# 20230827.net
KiCad netlist of a schematic drawn in EAGLE
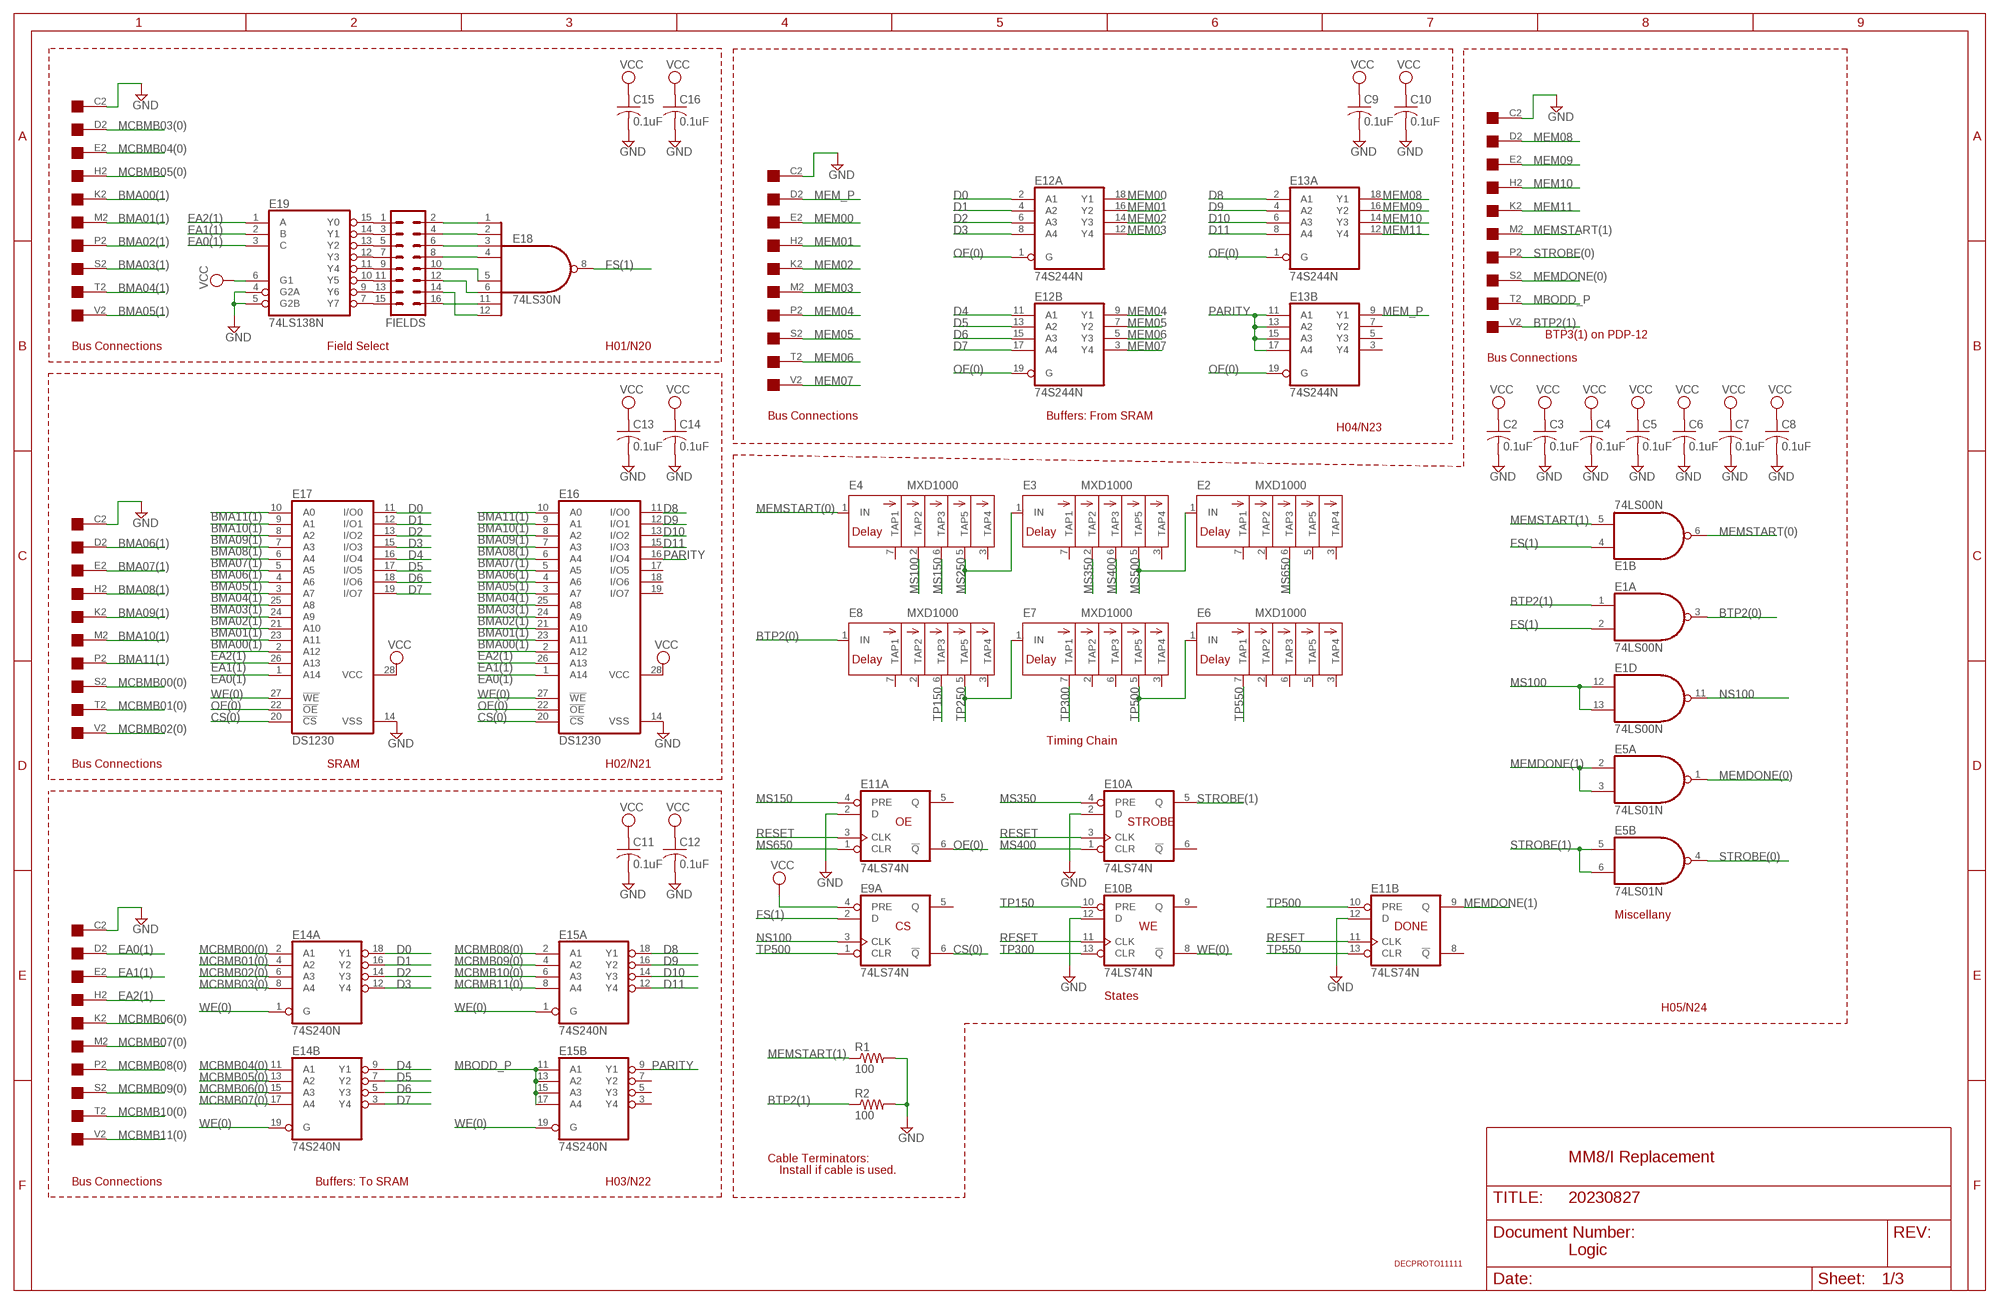
[diagram p0: schematic, sheet 1]
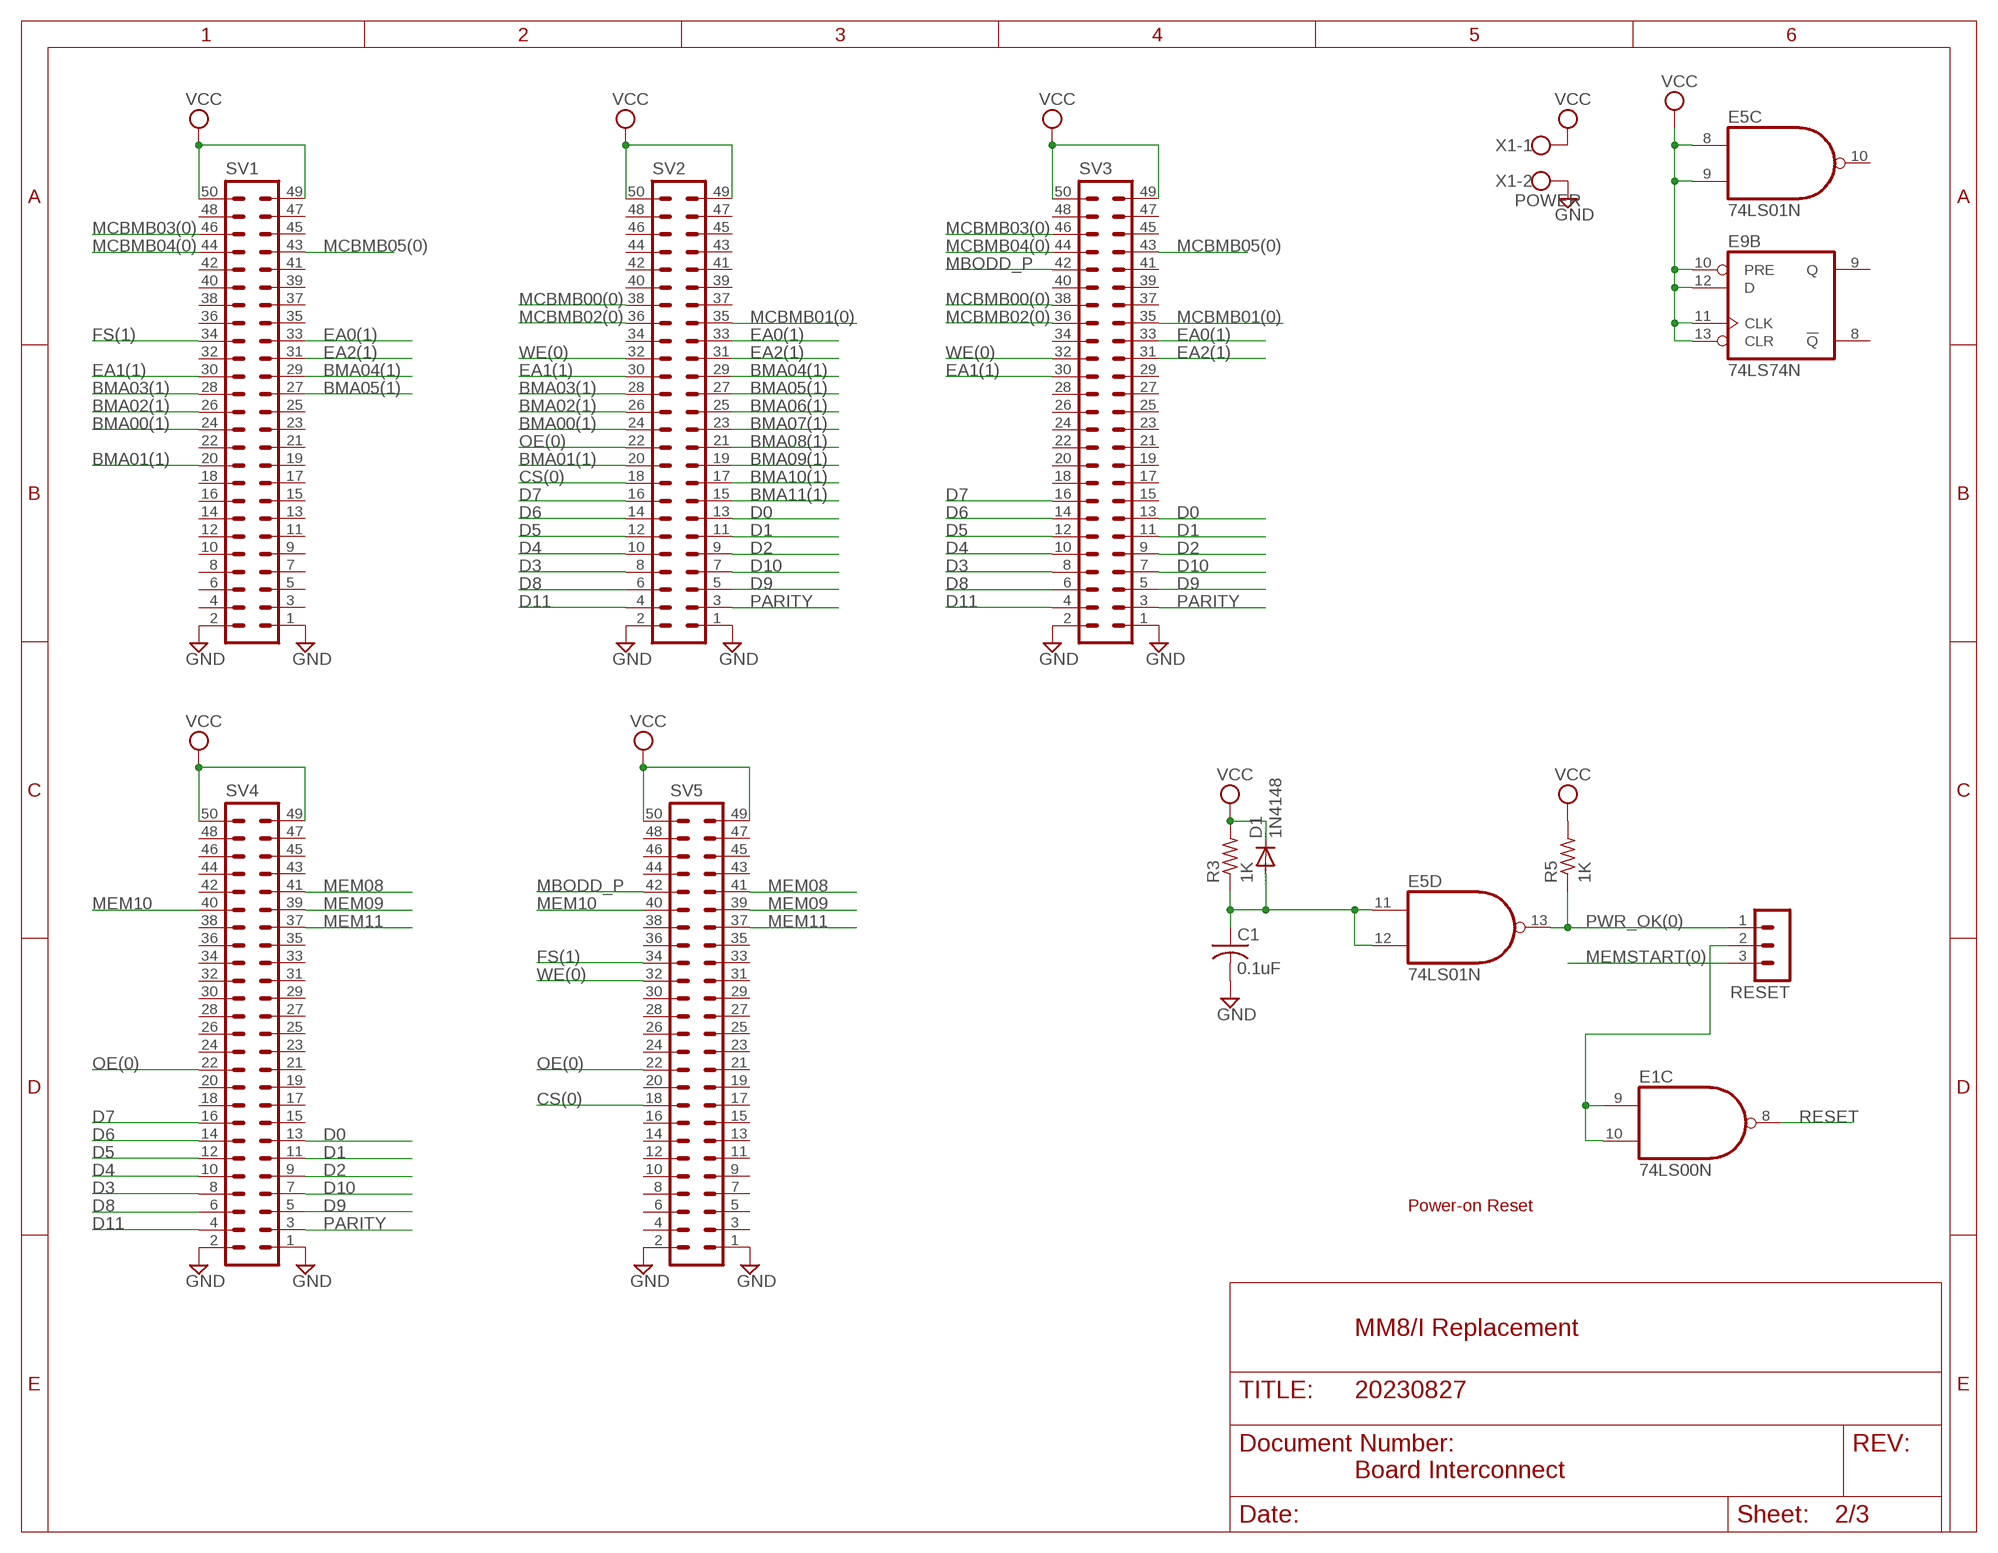
[diagram p1: schematic, sheet 2]
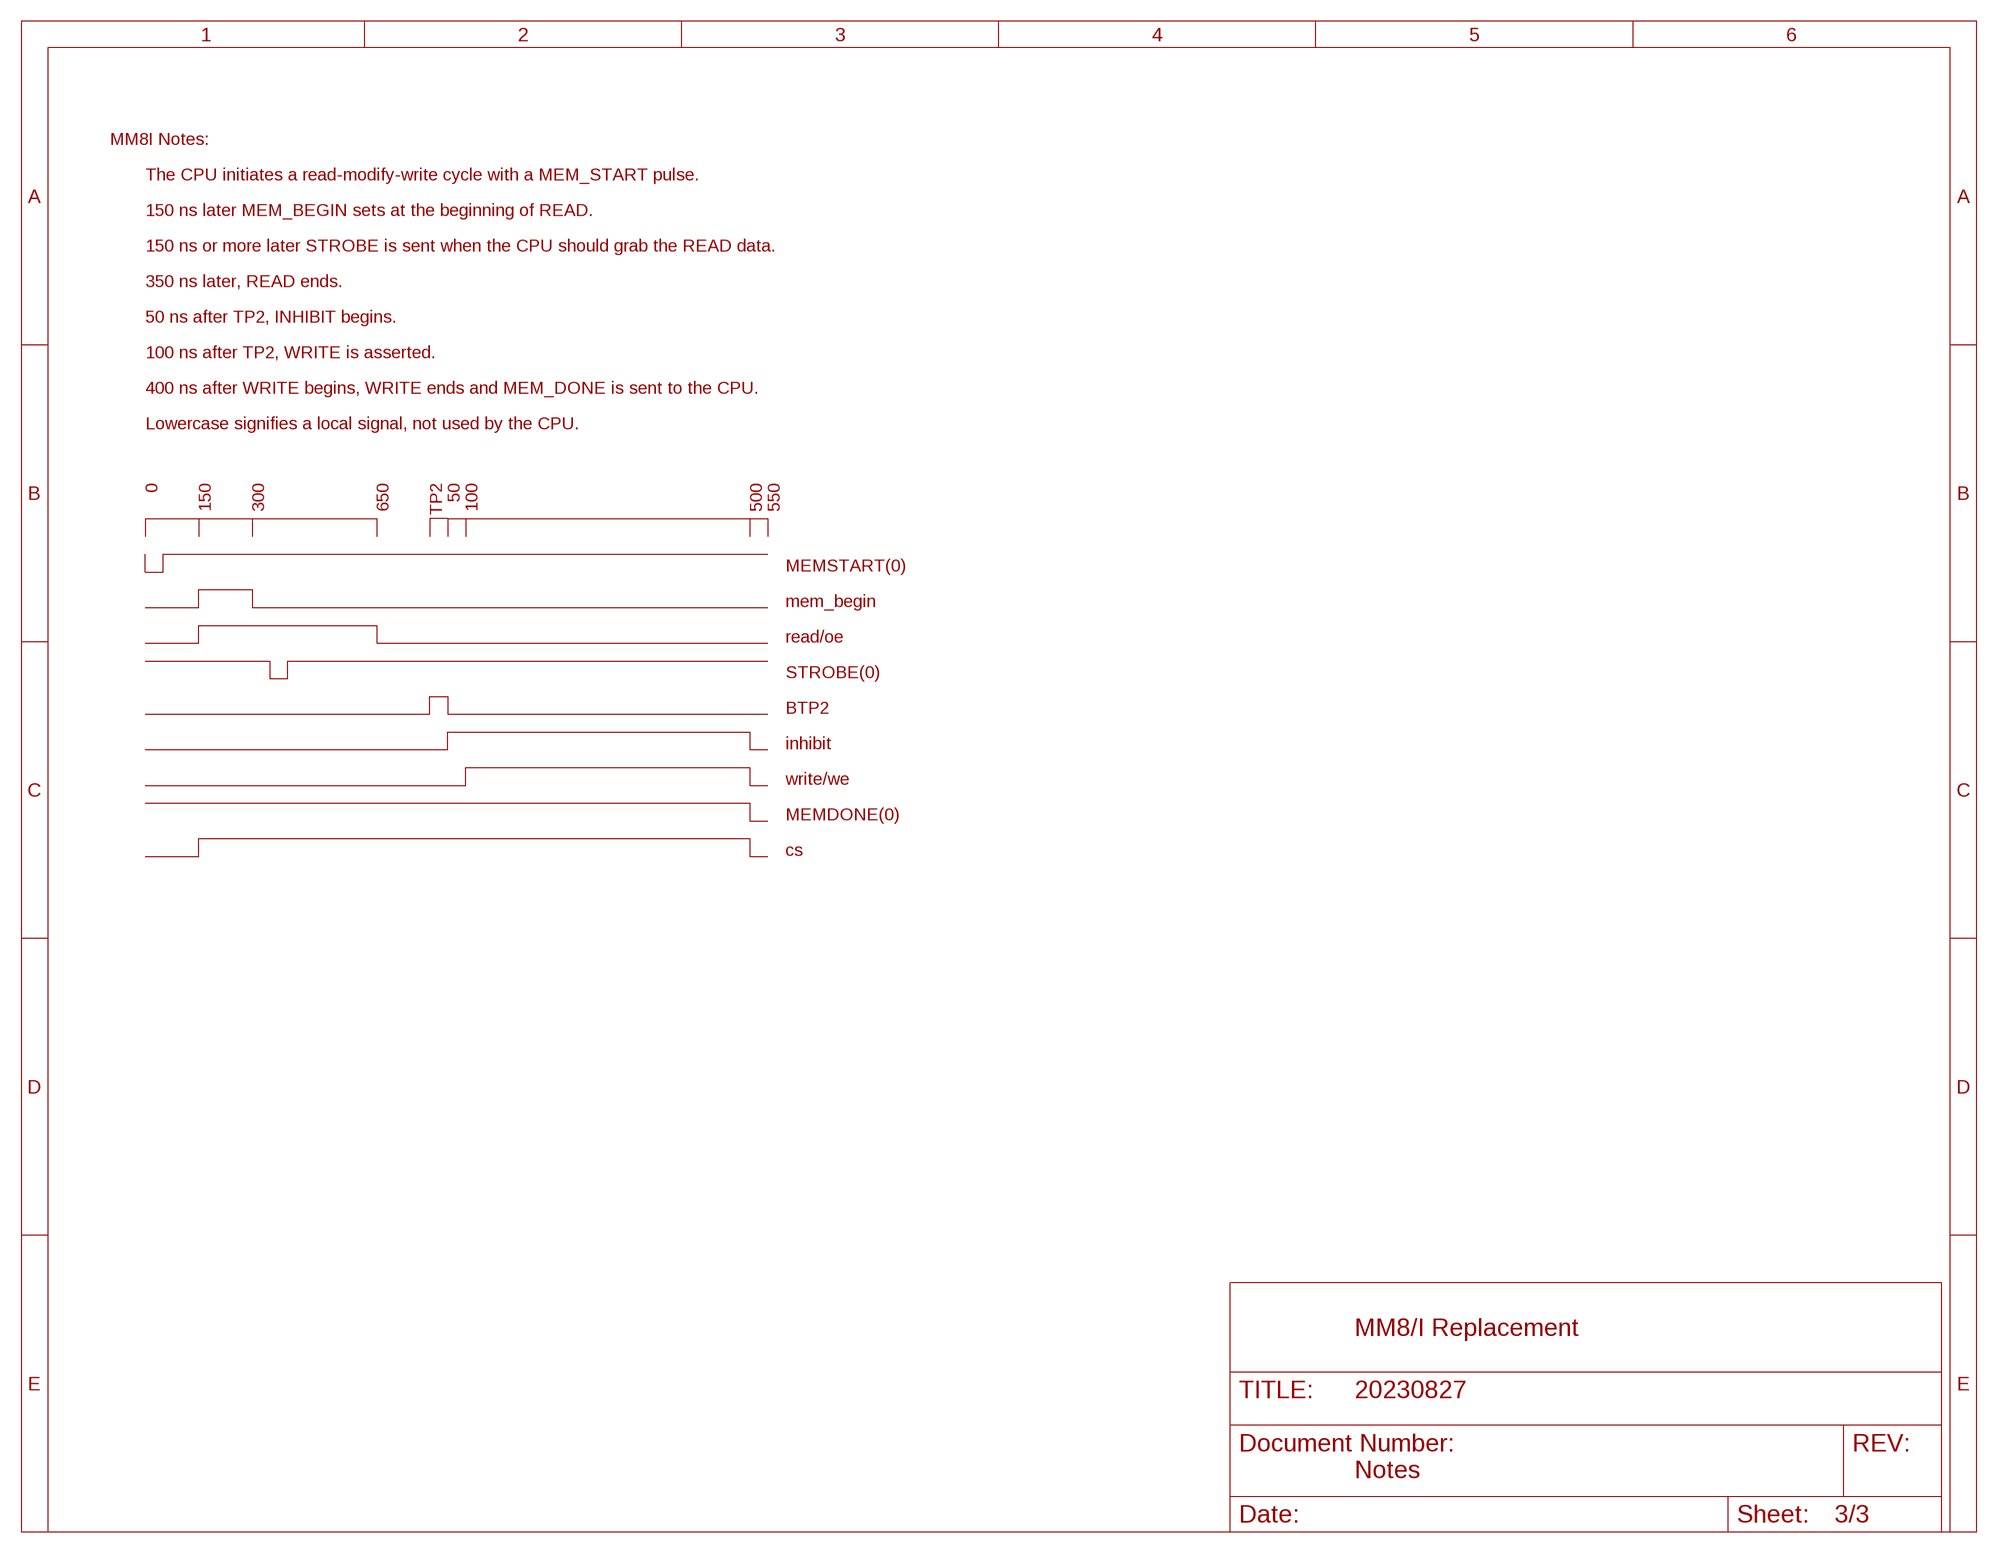
[diagram p2: schematic, sheet 3]

(export (version "E")
  (design (tool "Eeschema 10.0.6"))
  (components
    (comp (ref "C2")
      (value "0.1uF")
      (footprint "eagle-import:C050-025X075")
      (libsource (lib "eagle-import") (part "C-US050-025X075"))
    )
    (comp (ref "C3")
      (value "0.1uF")
      (footprint "eagle-import:C050-025X075")
      (libsource (lib "eagle-import") (part "C-US050-025X075"))
    )
    (comp (ref "C4")
      (value "0.1uF")
      (footprint "eagle-import:C050-025X075")
      (libsource (lib "eagle-import") (part "C-US050-025X075"))
    )
    (comp (ref "C5")
      (value "0.1uF")
      (footprint "eagle-import:C050-025X075")
      (libsource (lib "eagle-import") (part "C-US050-025X075"))
    )
    (comp (ref "C6")
      (value "0.1uF")
      (footprint "eagle-import:C050-025X075")
      (libsource (lib "eagle-import") (part "C-US050-025X075"))
    )
    (comp (ref "C7")
      (value "0.1uF")
      (footprint "eagle-import:C050-025X075")
      (libsource (lib "eagle-import") (part "C-US050-025X075"))
    )
    (comp (ref "C8")
      (value "0.1uF")
      (footprint "eagle-import:C050-025X075")
      (libsource (lib "eagle-import") (part "C-US050-025X075"))
    )
    (comp (ref "C9")
      (value "0.1uF")
      (footprint "eagle-import:C050-025X075")
      (libsource (lib "eagle-import") (part "C-US050-025X075"))
    )
    (comp (ref "C10")
      (value "0.1uF")
      (footprint "eagle-import:C050-025X075")
      (libsource (lib "eagle-import") (part "C-US050-025X075"))
    )
    (comp (ref "C11")
      (value "0.1uF")
      (footprint "eagle-import:C050-025X075")
      (libsource (lib "eagle-import") (part "C-US050-025X075"))
    )
    (comp (ref "C12")
      (value "0.1uF")
      (footprint "eagle-import:C050-025X075")
      (libsource (lib "eagle-import") (part "C-US050-025X075"))
    )
    (comp (ref "C13")
      (value "0.1uF")
      (footprint "eagle-import:C050-025X075")
      (libsource (lib "eagle-import") (part "C-US050-025X075"))
    )
    (comp (ref "C14")
      (value "0.1uF")
      (footprint "eagle-import:C050-025X075")
      (libsource (lib "eagle-import") (part "C-US050-025X075"))
    )
    (comp (ref "C15")
      (value "0.1uF")
      (footprint "eagle-import:C050-025X075")
      (libsource (lib "eagle-import") (part "C-US050-025X075"))
    )
    (comp (ref "C16")
      (value "0.1uF")
      (footprint "eagle-import:C050-025X075")
      (libsource (lib "eagle-import") (part "C-US050-025X075"))
    )
    (comp (ref "E1")
      (value "74LS00N")
      (footprint "eagle-import:DIL14")
      (libsource (lib "eagle-import") (part "7400NLS"))
    )
    (comp (ref "E2")
      (value "MXD1000")
      (footprint "eagle-import:DIL08")
      (libsource (lib "eagle-import") (part "MXD1000"))
    )
    (comp (ref "E3")
      (value "MXD1000")
      (footprint "eagle-import:DIL08")
      (libsource (lib "eagle-import") (part "MXD1000"))
    )
    (comp (ref "E4")
      (value "MXD1000")
      (footprint "eagle-import:DIL08")
      (libsource (lib "eagle-import") (part "MXD1000"))
    )
    (comp (ref "E5")
      (value "74LS01N")
      (footprint "eagle-import:DIL14")
      (libsource (lib "eagle-import") (part "7401NLS"))
    )
    (comp (ref "E6")
      (value "MXD1000")
      (footprint "eagle-import:DIL08")
      (libsource (lib "eagle-import") (part "MXD1000"))
    )
    (comp (ref "E7")
      (value "MXD1000")
      (footprint "eagle-import:DIL08")
      (libsource (lib "eagle-import") (part "MXD1000"))
    )
    (comp (ref "E8")
      (value "MXD1000")
      (footprint "eagle-import:DIL08")
      (libsource (lib "eagle-import") (part "MXD1000"))
    )
    (comp (ref "E9")
      (value "74LS74N")
      (footprint "eagle-import:DIL14")
      (libsource (lib "eagle-import") (part "7474NLS"))
    )
    (comp (ref "E10")
      (value "74LS74N")
      (footprint "eagle-import:DIL14")
      (libsource (lib "eagle-import") (part "7474NLS"))
    )
    (comp (ref "E11")
      (value "74LS74N")
      (footprint "eagle-import:DIL14")
      (libsource (lib "eagle-import") (part "7474NLS"))
    )
    (comp (ref "E12")
      (value "74S244N")
      (footprint "eagle-import:DIL20")
      (libsource (lib "eagle-import") (part "74244NS"))
    )
    (comp (ref "E13")
      (value "74S244N")
      (footprint "eagle-import:DIL20")
      (libsource (lib "eagle-import") (part "74244NS"))
    )
    (comp (ref "E14")
      (value "74S240N")
      (footprint "eagle-import:DIL20")
      (libsource (lib "eagle-import") (part "74240NS"))
    )
    (comp (ref "E15")
      (value "74S240N")
      (footprint "eagle-import:DIL20")
      (libsource (lib "eagle-import") (part "74240NS"))
    )
    (comp (ref "E16")
      (value "DS1230")
      (footprint "eagle-import:DIL28-6")
      (libsource (lib "eagle-import") (part "62256P"))
    )
    (comp (ref "E17")
      (value "DS1230")
      (footprint "eagle-import:DIL28-6")
      (libsource (lib "eagle-import") (part "62256P"))
    )
    (comp (ref "E18")
      (value "74LS30N")
      (footprint "eagle-import:DIL14")
      (libsource (lib "eagle-import") (part "7430NLS"))
    )
    (comp (ref "E19")
      (value "74LS138N")
      (footprint "eagle-import:DIL16")
      (libsource (lib "eagle-import") (part "74138NLS"))
    )
    (comp (ref "FIELDS")
      (value "MA08-2")
      (footprint "eagle-import:MA08-2")
      (libsource (lib "eagle-import") (part "MA08-2"))
    )
    (comp (ref "H01")
      (value "EDGE-1")
      (footprint "eagle-import:EDGE-CON1")
      (libsource (lib "eagle-import") (part "EDGE-1"))
    )
    (comp (ref "H02")
      (value "EDGE-1")
      (footprint "eagle-import:EDGE-CON1")
      (libsource (lib "eagle-import") (part "EDGE-1"))
    )
    (comp (ref "H03")
      (value "EDGE-1")
      (footprint "eagle-import:EDGE-CON1")
      (libsource (lib "eagle-import") (part "EDGE-1"))
    )
    (comp (ref "H04")
      (value "EDGE-1")
      (footprint "eagle-import:EDGE-CON1")
      (libsource (lib "eagle-import") (part "EDGE-1"))
    )
    (comp (ref "H05")
      (value "EDGE-1")
      (footprint "eagle-import:EDGE-CON1")
      (libsource (lib "eagle-import") (part "EDGE-1"))
    )
    (comp (ref "R1")
      (value "100")
      (footprint "eagle-import:0207_10")
      (libsource (lib "eagle-import") (part "R-US_0207/10"))
    )
    (comp (ref "R2")
      (value "100")
      (footprint "eagle-import:0207_10")
      (libsource (lib "eagle-import") (part "R-US_0207/10"))
    )
    (comp (ref "U$6")
      (value "DECPROTO11111")
      (footprint "eagle-import:DECPROTO11111")
      (libsource (lib "eagle-import") (part "DECPROTO11111"))
    )
    (comp (ref "C1")
      (value "0.1uF")
      (footprint "eagle-import:C050-025X075")
      (libsource (lib "eagle-import") (part "C-US050-025X075"))
    )
    (comp (ref "D1")
      (value "1N4148")
      (footprint "eagle-import:DO35-10")
      (libsource (lib "eagle-import") (part "1N4148DO35-10"))
    )
    (comp (ref "R3")
      (value "1K")
      (footprint "eagle-import:0207_10")
      (libsource (lib "eagle-import") (part "R-US_0207/10"))
    )
    (comp (ref "R5")
      (value "1K")
      (footprint "eagle-import:0207_10")
      (libsource (lib "eagle-import") (part "R-US_0207/10"))
    )
    (comp (ref "RESET")
      (value "MA03-1")
      (footprint "eagle-import:MA03-1")
      (libsource (lib "eagle-import") (part "MA03-1"))
    )
    (comp (ref "SV1")
      (value "ML50L")
      (footprint "eagle-import:ML50L")
      (libsource (lib "eagle-import") (part "ML50L"))
    )
    (comp (ref "SV2")
      (value "ML50L")
      (footprint "eagle-import:ML50L")
      (libsource (lib "eagle-import") (part "ML50L"))
    )
    (comp (ref "SV3")
      (value "ML50L")
      (footprint "eagle-import:ML50L")
      (libsource (lib "eagle-import") (part "ML50L"))
    )
    (comp (ref "SV4")
      (value "ML50L")
      (footprint "eagle-import:ML50L")
      (libsource (lib "eagle-import") (part "ML50L"))
    )
    (comp (ref "SV5")
      (value "ML50L")
      (footprint "eagle-import:ML50L")
      (libsource (lib "eagle-import") (part "ML50L"))
    )
    (comp (ref "X1")
      (value "POWER")
      (footprint "eagle-import:W237-102")
      (fields (field (name "MPN") "237-102"))
      (libsource (lib "eagle-import") (part "W237-102"))
    )
  )
  (nets
    (net (code "1") (name "BMA00(1)") (class "Default")
      (node (ref "E16") (pin "23") (pinfunction "A11_23") (pintype "input"))
      (node (ref "E17") (pin "23") (pinfunction "A11_23") (pintype "input"))
      (node (ref "H01") (pin "K2") (pinfunction "1_K2") (pintype "bidirectional"))
      (node (ref "SV1") (pin "24") (pinfunction "24_24") (pintype "passive"))
      (node (ref "SV2") (pin "24") (pinfunction "24_24") (pintype "passive"))
    )
    (net (code "2") (name "BMA01(1)") (class "Default")
      (node (ref "E16") (pin "21") (pinfunction "A10_21") (pintype "input"))
      (node (ref "E17") (pin "21") (pinfunction "A10_21") (pintype "input"))
      (node (ref "H01") (pin "M2") (pinfunction "1_M2") (pintype "bidirectional"))
      (node (ref "SV1") (pin "20") (pinfunction "20_20") (pintype "passive"))
      (node (ref "SV2") (pin "20") (pinfunction "20_20") (pintype "passive"))
    )
    (net (code "3") (name "BMA02(1)") (class "Default")
      (node (ref "E16") (pin "24") (pinfunction "A9_24") (pintype "input"))
      (node (ref "E17") (pin "24") (pinfunction "A9_24") (pintype "input"))
      (node (ref "H01") (pin "P2") (pinfunction "1_P2") (pintype "bidirectional"))
      (node (ref "SV1") (pin "26") (pinfunction "26_26") (pintype "passive"))
      (node (ref "SV2") (pin "26") (pinfunction "26_26") (pintype "passive"))
    )
    (net (code "4") (name "BMA03(1)") (class "Default")
      (node (ref "E16") (pin "25") (pinfunction "A8_25") (pintype "input"))
      (node (ref "E17") (pin "25") (pinfunction "A8_25") (pintype "input"))
      (node (ref "H01") (pin "S2") (pinfunction "1_S2") (pintype "bidirectional"))
      (node (ref "SV1") (pin "28") (pinfunction "28_28") (pintype "passive"))
      (node (ref "SV2") (pin "28") (pinfunction "28_28") (pintype "passive"))
    )
    (net (code "5") (name "BMA04(1)") (class "Default")
      (node (ref "E16") (pin "3") (pinfunction "A7_3") (pintype "input"))
      (node (ref "E17") (pin "3") (pinfunction "A7_3") (pintype "input"))
      (node (ref "H01") (pin "T2") (pinfunction "1_T2") (pintype "bidirectional"))
      (node (ref "SV1") (pin "29") (pinfunction "29_29") (pintype "passive"))
      (node (ref "SV2") (pin "29") (pinfunction "29_29") (pintype "passive"))
    )
    (net (code "6") (name "BMA05(1)") (class "Default")
      (node (ref "E16") (pin "4") (pinfunction "A6_4") (pintype "input"))
      (node (ref "E17") (pin "4") (pinfunction "A6_4") (pintype "input"))
      (node (ref "H01") (pin "V2") (pinfunction "1_V2") (pintype "bidirectional"))
      (node (ref "SV1") (pin "27") (pinfunction "27_27") (pintype "passive"))
      (node (ref "SV2") (pin "27") (pinfunction "27_27") (pintype "passive"))
    )
    (net (code "7") (name "BMA06(1)") (class "Default")
      (node (ref "E16") (pin "5") (pinfunction "A5_5") (pintype "input"))
      (node (ref "E17") (pin "5") (pinfunction "A5_5") (pintype "input"))
      (node (ref "H02") (pin "D2") (pinfunction "1_D2") (pintype "bidirectional"))
      (node (ref "SV2") (pin "25") (pinfunction "25_25") (pintype "passive"))
    )
    (net (code "8") (name "BMA07(1)") (class "Default")
      (node (ref "E16") (pin "6") (pinfunction "A4_6") (pintype "input"))
      (node (ref "E17") (pin "6") (pinfunction "A4_6") (pintype "input"))
      (node (ref "H02") (pin "E2") (pinfunction "1_E2") (pintype "bidirectional"))
      (node (ref "SV2") (pin "23") (pinfunction "23_23") (pintype "passive"))
    )
    (net (code "9") (name "BMA08(1)") (class "Default")
      (node (ref "E16") (pin "7") (pinfunction "A3_7") (pintype "input"))
      (node (ref "E17") (pin "7") (pinfunction "A3_7") (pintype "input"))
      (node (ref "H02") (pin "H2") (pinfunction "1_H2") (pintype "bidirectional"))
      (node (ref "SV2") (pin "21") (pinfunction "21_21") (pintype "passive"))
    )
    (net (code "10") (name "BMA09(1)") (class "Default")
      (node (ref "E16") (pin "8") (pinfunction "A2_8") (pintype "input"))
      (node (ref "E17") (pin "8") (pinfunction "A2_8") (pintype "input"))
      (node (ref "H02") (pin "K2") (pinfunction "1_K2") (pintype "bidirectional"))
      (node (ref "SV2") (pin "19") (pinfunction "19_19") (pintype "passive"))
    )
    (net (code "11") (name "BMA10(1)") (class "Default")
      (node (ref "E16") (pin "9") (pinfunction "A1_9") (pintype "input"))
      (node (ref "E17") (pin "9") (pinfunction "A1_9") (pintype "input"))
      (node (ref "H02") (pin "M2") (pinfunction "1_M2") (pintype "bidirectional"))
      (node (ref "SV2") (pin "17") (pinfunction "17_17") (pintype "passive"))
    )
    (net (code "12") (name "BMA11(1)") (class "Default")
      (node (ref "E16") (pin "10") (pinfunction "A0_10") (pintype "input"))
      (node (ref "E17") (pin "10") (pinfunction "A0_10") (pintype "input"))
      (node (ref "H02") (pin "P2") (pinfunction "1_P2") (pintype "bidirectional"))
      (node (ref "SV2") (pin "15") (pinfunction "15_15") (pintype "passive"))
    )
    (net (code "13") (name "BTP2(0)") (class "Default")
      (node (ref "E1") (pin "3") (pinfunction "O_3") (pintype "output"))
      (node (ref "E8") (pin "1") (pinfunction "IN_1") (pintype "input"))
    )
    (net (code "14") (name "BTP2(1)") (class "Default")
      (node (ref "E1") (pin "1") (pinfunction "I0_1") (pintype "input"))
      (node (ref "H05") (pin "V2") (pinfunction "1_V2") (pintype "bidirectional"))
      (node (ref "R2") (pin "1") (pinfunction "1_1") (pintype "passive"))
    )
    (net (code "15") (name "CS(0)") (class "Default")
      (node (ref "E16") (pin "20") (pinfunction "~{CS}_20") (pintype "input"))
      (node (ref "E17") (pin "20") (pinfunction "~{CS}_20") (pintype "input"))
      (node (ref "E9") (pin "6") (pinfunction "~{Q}_6") (pintype "output"))
      (node (ref "SV2") (pin "18") (pinfunction "18_18") (pintype "passive"))
      (node (ref "SV5") (pin "18") (pinfunction "18_18") (pintype "passive"))
    )
    (net (code "16") (name "D0") (class "Default")
      (node (ref "E12") (pin "2") (pinfunction "A1_2") (pintype "input"))
      (node (ref "E14") (pin "18") (pinfunction "Y1_18") (pintype "tri_state"))
      (node (ref "E17") (pin "11") (pinfunction "I/O0_11") (pintype "bidirectional"))
      (node (ref "SV2") (pin "13") (pinfunction "13_13") (pintype "passive"))
      (node (ref "SV3") (pin "13") (pinfunction "13_13") (pintype "passive"))
      (node (ref "SV4") (pin "13") (pinfunction "13_13") (pintype "passive"))
    )
    (net (code "17") (name "D1") (class "Default")
      (node (ref "E12") (pin "4") (pinfunction "A2_4") (pintype "input"))
      (node (ref "E14") (pin "16") (pinfunction "Y2_16") (pintype "tri_state"))
      (node (ref "E17") (pin "12") (pinfunction "I/O1_12") (pintype "bidirectional"))
      (node (ref "SV2") (pin "11") (pinfunction "11_11") (pintype "passive"))
      (node (ref "SV3") (pin "11") (pinfunction "11_11") (pintype "passive"))
      (node (ref "SV4") (pin "11") (pinfunction "11_11") (pintype "passive"))
    )
    (net (code "18") (name "D2") (class "Default")
      (node (ref "E12") (pin "6") (pinfunction "A3_6") (pintype "input"))
      (node (ref "E14") (pin "14") (pinfunction "Y3_14") (pintype "tri_state"))
      (node (ref "E17") (pin "13") (pinfunction "I/O2_13") (pintype "bidirectional"))
      (node (ref "SV2") (pin "9") (pinfunction "9_9") (pintype "passive"))
      (node (ref "SV3") (pin "9") (pinfunction "9_9") (pintype "passive"))
      (node (ref "SV4") (pin "9") (pinfunction "9_9") (pintype "passive"))
    )
    (net (code "19") (name "D3") (class "Default")
      (node (ref "E12") (pin "8") (pinfunction "A4_8") (pintype "input"))
      (node (ref "E14") (pin "12") (pinfunction "Y4_12") (pintype "tri_state"))
      (node (ref "E17") (pin "15") (pinfunction "I/O3_15") (pintype "bidirectional"))
      (node (ref "SV2") (pin "8") (pinfunction "8_8") (pintype "passive"))
      (node (ref "SV3") (pin "8") (pinfunction "8_8") (pintype "passive"))
      (node (ref "SV4") (pin "8") (pinfunction "8_8") (pintype "passive"))
    )
    (net (code "20") (name "D4") (class "Default")
      (node (ref "E12") (pin "11") (pinfunction "A1_11") (pintype "input"))
      (node (ref "E14") (pin "9") (pinfunction "Y1_9") (pintype "tri_state"))
      (node (ref "E17") (pin "16") (pinfunction "I/O4_16") (pintype "bidirectional"))
      (node (ref "SV2") (pin "10") (pinfunction "10_10") (pintype "passive"))
      (node (ref "SV3") (pin "10") (pinfunction "10_10") (pintype "passive"))
      (node (ref "SV4") (pin "10") (pinfunction "10_10") (pintype "passive"))
    )
    (net (code "21") (name "D5") (class "Default")
      (node (ref "E12") (pin "13") (pinfunction "A2_13") (pintype "input"))
      (node (ref "E14") (pin "7") (pinfunction "Y2_7") (pintype "tri_state"))
      (node (ref "E17") (pin "17") (pinfunction "I/O5_17") (pintype "bidirectional"))
      (node (ref "SV2") (pin "12") (pinfunction "12_12") (pintype "passive"))
      (node (ref "SV3") (pin "12") (pinfunction "12_12") (pintype "passive"))
      (node (ref "SV4") (pin "12") (pinfunction "12_12") (pintype "passive"))
    )
    (net (code "22") (name "D6") (class "Default")
      (node (ref "E12") (pin "15") (pinfunction "A3_15") (pintype "input"))
      (node (ref "E14") (pin "5") (pinfunction "Y3_5") (pintype "tri_state"))
      (node (ref "E17") (pin "18") (pinfunction "I/O6_18") (pintype "bidirectional"))
      (node (ref "SV2") (pin "14") (pinfunction "14_14") (pintype "passive"))
      (node (ref "SV3") (pin "14") (pinfunction "14_14") (pintype "passive"))
      (node (ref "SV4") (pin "14") (pinfunction "14_14") (pintype "passive"))
    )
    (net (code "23") (name "D7") (class "Default")
      (node (ref "E12") (pin "17") (pinfunction "A4_17") (pintype "input"))
      (node (ref "E14") (pin "3") (pinfunction "Y4_3") (pintype "tri_state"))
      (node (ref "E17") (pin "19") (pinfunction "I/O7_19") (pintype "bidirectional"))
      (node (ref "SV2") (pin "16") (pinfunction "16_16") (pintype "passive"))
      (node (ref "SV3") (pin "16") (pinfunction "16_16") (pintype "passive"))
      (node (ref "SV4") (pin "16") (pinfunction "16_16") (pintype "passive"))
    )
    (net (code "24") (name "D8") (class "Default")
      (node (ref "E13") (pin "2") (pinfunction "A1_2") (pintype "input"))
      (node (ref "E15") (pin "18") (pinfunction "Y1_18") (pintype "tri_state"))
      (node (ref "E16") (pin "11") (pinfunction "I/O0_11") (pintype "bidirectional"))
      (node (ref "SV2") (pin "6") (pinfunction "6_6") (pintype "passive"))
      (node (ref "SV3") (pin "6") (pinfunction "6_6") (pintype "passive"))
      (node (ref "SV4") (pin "6") (pinfunction "6_6") (pintype "passive"))
    )
    (net (code "25") (name "D9") (class "Default")
      (node (ref "E13") (pin "4") (pinfunction "A2_4") (pintype "input"))
      (node (ref "E15") (pin "16") (pinfunction "Y2_16") (pintype "tri_state"))
      (node (ref "E16") (pin "12") (pinfunction "I/O1_12") (pintype "bidirectional"))
      (node (ref "SV2") (pin "5") (pinfunction "5_5") (pintype "passive"))
      (node (ref "SV3") (pin "5") (pinfunction "5_5") (pintype "passive"))
      (node (ref "SV4") (pin "5") (pinfunction "5_5") (pintype "passive"))
    )
    (net (code "26") (name "D10") (class "Default")
      (node (ref "E13") (pin "6") (pinfunction "A3_6") (pintype "input"))
      (node (ref "E15") (pin "14") (pinfunction "Y3_14") (pintype "tri_state"))
      (node (ref "E16") (pin "13") (pinfunction "I/O2_13") (pintype "bidirectional"))
      (node (ref "SV2") (pin "7") (pinfunction "7_7") (pintype "passive"))
      (node (ref "SV3") (pin "7") (pinfunction "7_7") (pintype "passive"))
      (node (ref "SV4") (pin "7") (pinfunction "7_7") (pintype "passive"))
    )
    (net (code "27") (name "D11") (class "Default")
      (node (ref "E13") (pin "8") (pinfunction "A4_8") (pintype "input"))
      (node (ref "E15") (pin "12") (pinfunction "Y4_12") (pintype "tri_state"))
      (node (ref "E16") (pin "15") (pinfunction "I/O3_15") (pintype "bidirectional"))
      (node (ref "SV2") (pin "4") (pinfunction "4_4") (pintype "passive"))
      (node (ref "SV3") (pin "4") (pinfunction "4_4") (pintype "passive"))
      (node (ref "SV4") (pin "4") (pinfunction "4_4") (pintype "passive"))
    )
    (net (code "28") (name "EA0(1)") (class "Default")
      (node (ref "E16") (pin "1") (pinfunction "A14_1") (pintype "input"))
      (node (ref "E17") (pin "1") (pinfunction "A14_1") (pintype "input"))
      (node (ref "E19") (pin "3") (pinfunction "C_3") (pintype "input"))
      (node (ref "H03") (pin "D2") (pinfunction "1_D2") (pintype "bidirectional"))
      (node (ref "SV1") (pin "33") (pinfunction "33_33") (pintype "passive"))
      (node (ref "SV2") (pin "33") (pinfunction "33_33") (pintype "passive"))
      (node (ref "SV3") (pin "33") (pinfunction "33_33") (pintype "passive"))
    )
    (net (code "29") (name "EA1(1)") (class "Default")
      (node (ref "E16") (pin "26") (pinfunction "A13_26") (pintype "input"))
      (node (ref "E17") (pin "26") (pinfunction "A13_26") (pintype "input"))
      (node (ref "E19") (pin "2") (pinfunction "B_2") (pintype "input"))
      (node (ref "H03") (pin "E2") (pinfunction "1_E2") (pintype "bidirectional"))
      (node (ref "SV1") (pin "30") (pinfunction "30_30") (pintype "passive"))
      (node (ref "SV2") (pin "30") (pinfunction "30_30") (pintype "passive"))
      (node (ref "SV3") (pin "30") (pinfunction "30_30") (pintype "passive"))
    )
    (net (code "30") (name "EA2(1)") (class "Default")
      (node (ref "E16") (pin "2") (pinfunction "A12_2") (pintype "input"))
      (node (ref "E17") (pin "2") (pinfunction "A12_2") (pintype "input"))
      (node (ref "E19") (pin "1") (pinfunction "A_1") (pintype "input"))
      (node (ref "H03") (pin "H2") (pinfunction "1_H2") (pintype "bidirectional"))
      (node (ref "SV1") (pin "31") (pinfunction "31_31") (pintype "passive"))
      (node (ref "SV2") (pin "31") (pinfunction "31_31") (pintype "passive"))
      (node (ref "SV3") (pin "31") (pinfunction "31_31") (pintype "passive"))
    )
    (net (code "31") (name "FS(1)") (class "Default")
      (node (ref "E1") (pin "2") (pinfunction "I1_2") (pintype "input"))
      (node (ref "E1") (pin "4") (pinfunction "I0_4") (pintype "input"))
      (node (ref "E18") (pin "8") (pinfunction "O_8") (pintype "output"))
      (node (ref "E9") (pin "2") (pinfunction "D_2") (pintype "input"))
      (node (ref "SV1") (pin "34") (pinfunction "34_34") (pintype "passive"))
      (node (ref "SV5") (pin "34") (pinfunction "34_34") (pintype "passive"))
    )
    (net (code "32") (name "GND") (class "Default")
      (node (ref "C1") (pin "2") (pinfunction "2_2") (pintype "passive"))
      (node (ref "C10") (pin "2") (pinfunction "2_2") (pintype "passive"))
      (node (ref "C11") (pin "2") (pinfunction "2_2") (pintype "passive"))
      (node (ref "C12") (pin "2") (pinfunction "2_2") (pintype "passive"))
      (node (ref "C13") (pin "2") (pinfunction "2_2") (pintype "passive"))
      (node (ref "C14") (pin "2") (pinfunction "2_2") (pintype "passive"))
      (node (ref "C15") (pin "2") (pinfunction "2_2") (pintype "passive"))
      (node (ref "C16") (pin "2") (pinfunction "2_2") (pintype "passive"))
      (node (ref "C2") (pin "2") (pinfunction "2_2") (pintype "passive"))
      (node (ref "C3") (pin "2") (pinfunction "2_2") (pintype "passive"))
      (node (ref "C4") (pin "2") (pinfunction "2_2") (pintype "passive"))
      (node (ref "C5") (pin "2") (pinfunction "2_2") (pintype "passive"))
      (node (ref "C6") (pin "2") (pinfunction "2_2") (pintype "passive"))
      (node (ref "C7") (pin "2") (pinfunction "2_2") (pintype "passive"))
      (node (ref "C8") (pin "2") (pinfunction "2_2") (pintype "passive"))
      (node (ref "C9") (pin "2") (pinfunction "2_2") (pintype "passive"))
      (node (ref "E10") (pin "12") (pinfunction "D_12") (pintype "input"))
      (node (ref "E10") (pin "2") (pinfunction "D_2") (pintype "input"))
      (node (ref "E11") (pin "12") (pinfunction "D_12") (pintype "input"))
      (node (ref "E11") (pin "2") (pinfunction "D_2") (pintype "input"))
      (node (ref "E16") (pin "14") (pinfunction "VSS_14") (pintype "power_in"))
      (node (ref "E17") (pin "14") (pinfunction "VSS_14") (pintype "power_in"))
      (node (ref "E19") (pin "4") (pinfunction "G2A_4") (pintype "input"))
      (node (ref "E19") (pin "5") (pinfunction "G2B_5") (pintype "input"))
      (node (ref "H01") (pin "C2") (pinfunction "1_C2") (pintype "bidirectional"))
      (node (ref "H02") (pin "C2") (pinfunction "1_C2") (pintype "bidirectional"))
      (node (ref "H03") (pin "C2") (pinfunction "1_C2") (pintype "bidirectional"))
      (node (ref "H04") (pin "C2") (pinfunction "1_C2") (pintype "bidirectional"))
      (node (ref "H05") (pin "C2") (pinfunction "1_C2") (pintype "bidirectional"))
      (node (ref "R1") (pin "2") (pinfunction "2_2") (pintype "passive"))
      (node (ref "R2") (pin "2") (pinfunction "2_2") (pintype "passive"))
      (node (ref "SV1") (pin "1") (pinfunction "1_1") (pintype "passive"))
      (node (ref "SV1") (pin "2") (pinfunction "2_2") (pintype "passive"))
      (node (ref "SV2") (pin "1") (pinfunction "1_1") (pintype "passive"))
      (node (ref "SV2") (pin "2") (pinfunction "2_2") (pintype "passive"))
      (node (ref "SV3") (pin "1") (pinfunction "1_1") (pintype "passive"))
      (node (ref "SV3") (pin "2") (pinfunction "2_2") (pintype "passive"))
      (node (ref "SV4") (pin "1") (pinfunction "1_1") (pintype "passive"))
      (node (ref "SV4") (pin "2") (pinfunction "2_2") (pintype "passive"))
      (node (ref "SV5") (pin "1") (pinfunction "1_1") (pintype "passive"))
      (node (ref "SV5") (pin "2") (pinfunction "2_2") (pintype "passive"))
      (node (ref "X1") (pin "2") (pinfunction "KL_2") (pintype "passive"))
    )
    (net (code "33") (name "MBODD_P") (class "Default")
      (node (ref "E15") (pin "11") (pinfunction "A1_11") (pintype "input"))
      (node (ref "E15") (pin "13") (pinfunction "A2_13") (pintype "input"))
      (node (ref "E15") (pin "15") (pinfunction "A3_15") (pintype "input"))
      (node (ref "E15") (pin "17") (pinfunction "A4_17") (pintype "input"))
      (node (ref "H05") (pin "T2") (pinfunction "1_T2") (pintype "bidirectional"))
      (node (ref "SV3") (pin "42") (pinfunction "42_42") (pintype "passive"))
      (node (ref "SV5") (pin "42") (pinfunction "42_42") (pintype "passive"))
    )
    (net (code "34") (name "MCBMB00(0)") (class "Default")
      (node (ref "E14") (pin "2") (pinfunction "A1_2") (pintype "input"))
      (node (ref "H02") (pin "S2") (pinfunction "1_S2") (pintype "bidirectional"))
      (node (ref "SV2") (pin "38") (pinfunction "38_38") (pintype "passive"))
      (node (ref "SV3") (pin "38") (pinfunction "38_38") (pintype "passive"))
    )
    (net (code "35") (name "MCBMB01(0)") (class "Default")
      (node (ref "E14") (pin "4") (pinfunction "A2_4") (pintype "input"))
      (node (ref "H02") (pin "T2") (pinfunction "1_T2") (pintype "bidirectional"))
      (node (ref "SV2") (pin "35") (pinfunction "35_35") (pintype "passive"))
      (node (ref "SV3") (pin "35") (pinfunction "35_35") (pintype "passive"))
    )
    (net (code "36") (name "MCBMB02(0)") (class "Default")
      (node (ref "E14") (pin "6") (pinfunction "A3_6") (pintype "input"))
      (node (ref "H02") (pin "V2") (pinfunction "1_V2") (pintype "bidirectional"))
      (node (ref "SV2") (pin "36") (pinfunction "36_36") (pintype "passive"))
      (node (ref "SV3") (pin "36") (pinfunction "36_36") (pintype "passive"))
    )
    (net (code "37") (name "MCBMB03(0)") (class "Default")
      (node (ref "E14") (pin "8") (pinfunction "A4_8") (pintype "input"))
      (node (ref "H01") (pin "D2") (pinfunction "1_D2") (pintype "bidirectional"))
      (node (ref "SV1") (pin "46") (pinfunction "46_46") (pintype "passive"))
      (node (ref "SV3") (pin "46") (pinfunction "46_46") (pintype "passive"))
    )
    (net (code "38") (name "MCBMB04(0)") (class "Default")
      (node (ref "E14") (pin "11") (pinfunction "A1_11") (pintype "input"))
      (node (ref "H01") (pin "E2") (pinfunction "1_E2") (pintype "bidirectional"))
      (node (ref "SV1") (pin "44") (pinfunction "44_44") (pintype "passive"))
      (node (ref "SV3") (pin "44") (pinfunction "44_44") (pintype "passive"))
    )
    (net (code "39") (name "MCBMB05(0)") (class "Default")
      (node (ref "E14") (pin "13") (pinfunction "A2_13") (pintype "input"))
      (node (ref "H01") (pin "H2") (pinfunction "1_H2") (pintype "bidirectional"))
      (node (ref "SV1") (pin "43") (pinfunction "43_43") (pintype "passive"))
      (node (ref "SV3") (pin "43") (pinfunction "43_43") (pintype "passive"))
    )
    (net (code "40") (name "MCBMB06(0)") (class "Default")
      (node (ref "E14") (pin "15") (pinfunction "A3_15") (pintype "input"))
      (node (ref "H03") (pin "K2") (pinfunction "1_K2") (pintype "bidirectional"))
    )
    (net (code "41") (name "MCBMB07(0)") (class "Default")
      (node (ref "E14") (pin "17") (pinfunction "A4_17") (pintype "input"))
      (node (ref "H03") (pin "M2") (pinfunction "1_M2") (pintype "bidirectional"))
    )
    (net (code "42") (name "MCBMB08(0)") (class "Default")
      (node (ref "E15") (pin "2") (pinfunction "A1_2") (pintype "input"))
      (node (ref "H03") (pin "P2") (pinfunction "1_P2") (pintype "bidirectional"))
    )
    (net (code "43") (name "MCBMB09(0)") (class "Default")
      (node (ref "E15") (pin "4") (pinfunction "A2_4") (pintype "input"))
      (node (ref "H03") (pin "S2") (pinfunction "1_S2") (pintype "bidirectional"))
    )
    (net (code "44") (name "MCBMB10(0)") (class "Default")
      (node (ref "E15") (pin "6") (pinfunction "A3_6") (pintype "input"))
      (node (ref "H03") (pin "T2") (pinfunction "1_T2") (pintype "bidirectional"))
    )
    (net (code "45") (name "MCBMB11(0)") (class "Default")
      (node (ref "E15") (pin "8") (pinfunction "A4_8") (pintype "input"))
      (node (ref "H03") (pin "V2") (pinfunction "1_V2") (pintype "bidirectional"))
    )
    (net (code "46") (name "MEM00") (class "Default")
      (node (ref "E12") (pin "18") (pinfunction "Y1_18") (pintype "tri_state"))
      (node (ref "H04") (pin "E2") (pinfunction "1_E2") (pintype "bidirectional"))
    )
    (net (code "47") (name "MEM01") (class "Default")
      (node (ref "E12") (pin "16") (pinfunction "Y2_16") (pintype "tri_state"))
      (node (ref "H04") (pin "H2") (pinfunction "1_H2") (pintype "bidirectional"))
    )
    (net (code "48") (name "MEM02") (class "Default")
      (node (ref "E12") (pin "14") (pinfunction "Y3_14") (pintype "tri_state"))
      (node (ref "H04") (pin "K2") (pinfunction "1_K2") (pintype "bidirectional"))
    )
    (net (code "49") (name "MEM03") (class "Default")
      (node (ref "E12") (pin "12") (pinfunction "Y4_12") (pintype "tri_state"))
      (node (ref "H04") (pin "M2") (pinfunction "1_M2") (pintype "bidirectional"))
    )
    (net (code "50") (name "MEM04") (class "Default")
      (node (ref "E12") (pin "9") (pinfunction "Y1_9") (pintype "tri_state"))
      (node (ref "H04") (pin "P2") (pinfunction "1_P2") (pintype "bidirectional"))
    )
    (net (code "51") (name "MEM05") (class "Default")
      (node (ref "E12") (pin "7") (pinfunction "Y2_7") (pintype "tri_state"))
      (node (ref "H04") (pin "S2") (pinfunction "1_S2") (pintype "bidirectional"))
    )
    (net (code "52") (name "MEM06") (class "Default")
      (node (ref "E12") (pin "5") (pinfunction "Y3_5") (pintype "tri_state"))
      (node (ref "H04") (pin "T2") (pinfunction "1_T2") (pintype "bidirectional"))
    )
    (net (code "53") (name "MEM07") (class "Default")
      (node (ref "E12") (pin "3") (pinfunction "Y4_3") (pintype "tri_state"))
      (node (ref "H04") (pin "V2") (pinfunction "1_V2") (pintype "bidirectional"))
    )
    (net (code "54") (name "MEM08") (class "Default")
      (node (ref "E13") (pin "18") (pinfunction "Y1_18") (pintype "tri_state"))
      (node (ref "H05") (pin "D2") (pinfunction "1_D2") (pintype "bidirectional"))
      (node (ref "SV4") (pin "41") (pinfunction "41_41") (pintype "passive"))
      (node (ref "SV5") (pin "41") (pinfunction "41_41") (pintype "passive"))
    )
    (net (code "55") (name "MEM09") (class "Default")
      (node (ref "E13") (pin "16") (pinfunction "Y2_16") (pintype "tri_state"))
      (node (ref "H05") (pin "E2") (pinfunction "1_E2") (pintype "bidirectional"))
      (node (ref "SV4") (pin "39") (pinfunction "39_39") (pintype "passive"))
      (node (ref "SV5") (pin "39") (pinfunction "39_39") (pintype "passive"))
    )
    (net (code "56") (name "MEM10") (class "Default")
      (node (ref "E13") (pin "14") (pinfunction "Y3_14") (pintype "tri_state"))
      (node (ref "H05") (pin "H2") (pinfunction "1_H2") (pintype "bidirectional"))
      (node (ref "SV4") (pin "40") (pinfunction "40_40") (pintype "passive"))
      (node (ref "SV5") (pin "40") (pinfunction "40_40") (pintype "passive"))
    )
    (net (code "57") (name "MEM11") (class "Default")
      (node (ref "E13") (pin "12") (pinfunction "Y4_12") (pintype "tri_state"))
      (node (ref "H05") (pin "K2") (pinfunction "1_K2") (pintype "bidirectional"))
      (node (ref "SV4") (pin "37") (pinfunction "37_37") (pintype "passive"))
      (node (ref "SV5") (pin "37") (pinfunction "37_37") (pintype "passive"))
    )
    (net (code "58") (name "MEMDONE(0)") (class "Default")
      (node (ref "E5") (pin "1") (pinfunction "O_1") (pintype "open_collector"))
      (node (ref "H05") (pin "S2") (pinfunction "1_S2") (pintype "bidirectional"))
    )
    (net (code "59") (name "MEMDONE(1)") (class "Default")
      (node (ref "E11") (pin "9") (pinfunction "Q_9") (pintype "output"))
      (node (ref "E5") (pin "2") (pinfunction "I0_2") (pintype "input"))
      (node (ref "E5") (pin "3") (pinfunction "I1_3") (pintype "input"))
    )
    (net (code "60") (name "MEMSTART(0)") (class "Default")
      (node (ref "E1") (pin "6") (pinfunction "O_6") (pintype "output"))
      (node (ref "E4") (pin "1") (pinfunction "IN_1") (pintype "input"))
      (node (ref "RESET") (pin "3") (pinfunction "3_3") (pintype "passive"))
    )
    (net (code "61") (name "MEMSTART(1)") (class "Default")
      (node (ref "E1") (pin "5") (pinfunction "I1_5") (pintype "input"))
      (node (ref "H05") (pin "M2") (pinfunction "1_M2") (pintype "bidirectional"))
      (node (ref "R1") (pin "1") (pinfunction "1_1") (pintype "passive"))
    )
    (net (code "62") (name "MEM_P") (class "Default")
      (node (ref "E13") (pin "9") (pinfunction "Y1_9") (pintype "tri_state"))
      (node (ref "H04") (pin "D2") (pinfunction "1_D2") (pintype "bidirectional"))
    )
    (net (code "63") (name "MS100") (class "Default")
      (node (ref "E1") (pin "12") (pinfunction "I0_12") (pintype "input"))
      (node (ref "E1") (pin "13") (pinfunction "I1_13") (pintype "input"))
      (node (ref "E4") (pin "2") (pinfunction "TAP2_2") (pintype "output"))
    )
    (net (code "64") (name "MS150") (class "Default")
      (node (ref "E11") (pin "4") (pinfunction "PRE_4") (pintype "input"))
      (node (ref "E4") (pin "6") (pinfunction "TAP3_6") (pintype "output"))
    )
    (net (code "65") (name "MS250") (class "Default")
      (node (ref "E3") (pin "1") (pinfunction "IN_1") (pintype "input"))
      (node (ref "E4") (pin "5") (pinfunction "TAP5_5") (pintype "output"))
    )
    (net (code "66") (name "MS350") (class "Default")
      (node (ref "E10") (pin "4") (pinfunction "PRE_4") (pintype "input"))
      (node (ref "E3") (pin "2") (pinfunction "TAP2_2") (pintype "output"))
    )
    (net (code "67") (name "MS400") (class "Default")
      (node (ref "E10") (pin "1") (pinfunction "CLR_1") (pintype "input"))
      (node (ref "E3") (pin "6") (pinfunction "TAP3_6") (pintype "output"))
    )
    (net (code "68") (name "MS500") (class "Default")
      (node (ref "E2") (pin "1") (pinfunction "IN_1") (pintype "input"))
      (node (ref "E3") (pin "5") (pinfunction "TAP5_5") (pintype "output"))
    )
    (net (code "69") (name "MS650") (class "Default")
      (node (ref "E11") (pin "1") (pinfunction "CLR_1") (pintype "input"))
      (node (ref "E2") (pin "6") (pinfunction "TAP3_6") (pintype "output"))
    )
    (net (code "70") (name "NS100") (class "Default")
      (node (ref "E1") (pin "11") (pinfunction "O_11") (pintype "output"))
      (node (ref "E9") (pin "3") (pinfunction "CLK_3") (pintype "input"))
    )
    (net (code "71") (name "Net-(E1C-I0)") (class "Default")
      (node (ref "E1") (pin "10") (pinfunction "I1_10") (pintype "input"))
      (node (ref "E1") (pin "9") (pinfunction "I0_9") (pintype "input"))
      (node (ref "RESET") (pin "2") (pinfunction "2_2") (pintype "passive"))
    )
    (net (code "72") (name "Net-(E5D-I0)") (class "Default")
      (node (ref "C1") (pin "1") (pinfunction "1_1") (pintype "passive"))
      (node (ref "D1") (pin "A") (pinfunction "A_A") (pintype "passive"))
      (node (ref "E5") (pin "11") (pinfunction "I0_11") (pintype "input"))
      (node (ref "E5") (pin "12") (pinfunction "I1_12") (pintype "input"))
      (node (ref "R3") (pin "1") (pinfunction "1_1") (pintype "passive"))
    )
    (net (code "73") (name "Net-(E18A-I0)") (class "Default")
      (node (ref "E18") (pin "1") (pinfunction "I0_1") (pintype "input"))
      (node (ref "FIELDS") (pin "2") (pinfunction "2_2") (pintype "passive"))
    )
    (net (code "74") (name "Net-(E18A-I1)") (class "Default")
      (node (ref "E18") (pin "2") (pinfunction "I1_2") (pintype "input"))
      (node (ref "FIELDS") (pin "4") (pinfunction "4_4") (pintype "passive"))
    )
    (net (code "75") (name "Net-(E18A-I2)") (class "Default")
      (node (ref "E18") (pin "3") (pinfunction "I2_3") (pintype "input"))
      (node (ref "FIELDS") (pin "6") (pinfunction "6_6") (pintype "passive"))
    )
    (net (code "76") (name "Net-(E18A-I3)") (class "Default")
      (node (ref "E18") (pin "4") (pinfunction "I3_4") (pintype "input"))
      (node (ref "FIELDS") (pin "8") (pinfunction "8_8") (pintype "passive"))
    )
    (net (code "77") (name "Net-(E18A-I4)") (class "Default")
      (node (ref "E18") (pin "5") (pinfunction "I4_5") (pintype "input"))
      (node (ref "FIELDS") (pin "10") (pinfunction "10_10") (pintype "passive"))
    )
    (net (code "78") (name "Net-(E18A-I5)") (class "Default")
      (node (ref "E18") (pin "6") (pinfunction "I5_6") (pintype "input"))
      (node (ref "FIELDS") (pin "12") (pinfunction "12_12") (pintype "passive"))
    )
    (net (code "79") (name "Net-(E18A-I6)") (class "Default")
      (node (ref "E18") (pin "11") (pinfunction "I6_11") (pintype "input"))
      (node (ref "FIELDS") (pin "16") (pinfunction "16_16") (pintype "passive"))
    )
    (net (code "80") (name "Net-(E18A-I7)") (class "Default")
      (node (ref "E18") (pin "12") (pinfunction "I7_12") (pintype "input"))
      (node (ref "FIELDS") (pin "14") (pinfunction "14_14") (pintype "passive"))
    )
    (net (code "81") (name "Net-(E19A-Y0)") (class "Default")
      (node (ref "E19") (pin "15") (pinfunction "Y0_15") (pintype "output"))
      (node (ref "FIELDS") (pin "1") (pinfunction "1_1") (pintype "passive"))
    )
    (net (code "82") (name "Net-(E19A-Y1)") (class "Default")
      (node (ref "E19") (pin "14") (pinfunction "Y1_14") (pintype "output"))
      (node (ref "FIELDS") (pin "3") (pinfunction "3_3") (pintype "passive"))
    )
    (net (code "83") (name "Net-(E19A-Y2)") (class "Default")
      (node (ref "E19") (pin "13") (pinfunction "Y2_13") (pintype "output"))
      (node (ref "FIELDS") (pin "5") (pinfunction "5_5") (pintype "passive"))
    )
    (net (code "84") (name "Net-(E19A-Y3)") (class "Default")
      (node (ref "E19") (pin "12") (pinfunction "Y3_12") (pintype "output"))
      (node (ref "FIELDS") (pin "7") (pinfunction "7_7") (pintype "passive"))
    )
    (net (code "85") (name "Net-(E19A-Y4)") (class "Default")
      (node (ref "E19") (pin "11") (pinfunction "Y4_11") (pintype "output"))
      (node (ref "FIELDS") (pin "9") (pinfunction "9_9") (pintype "passive"))
    )
    (net (code "86") (name "Net-(E19A-Y5)") (class "Default")
      (node (ref "E19") (pin "10") (pinfunction "Y5_10") (pintype "output"))
      (node (ref "FIELDS") (pin "11") (pinfunction "11_11") (pintype "passive"))
    )
    (net (code "87") (name "Net-(E19A-Y6)") (class "Default")
      (node (ref "E19") (pin "9") (pinfunction "Y6_9") (pintype "output"))
      (node (ref "FIELDS") (pin "13") (pinfunction "13_13") (pintype "passive"))
    )
    (net (code "88") (name "Net-(E19A-Y7)") (class "Default")
      (node (ref "E19") (pin "7") (pinfunction "Y7_7") (pintype "output"))
      (node (ref "FIELDS") (pin "15") (pinfunction "15_15") (pintype "passive"))
    )
    (net (code "89") (name "OE(0)") (class "Default")
      (node (ref "E11") (pin "6") (pinfunction "~{Q}_6") (pintype "output"))
      (node (ref "E12") (pin "1") (pinfunction "G_1") (pintype "input"))
      (node (ref "E12") (pin "19") (pinfunction "G_19") (pintype "input"))
      (node (ref "E13") (pin "1") (pinfunction "G_1") (pintype "input"))
      (node (ref "E13") (pin "19") (pinfunction "G_19") (pintype "input"))
      (node (ref "E16") (pin "22") (pinfunction "~{OE}_22") (pintype "input"))
      (node (ref "E17") (pin "22") (pinfunction "~{OE}_22") (pintype "input"))
      (node (ref "SV2") (pin "22") (pinfunction "22_22") (pintype "passive"))
      (node (ref "SV4") (pin "22") (pinfunction "22_22") (pintype "passive"))
      (node (ref "SV5") (pin "22") (pinfunction "22_22") (pintype "passive"))
    )
    (net (code "90") (name "PARITY") (class "Default")
      (node (ref "E13") (pin "11") (pinfunction "A1_11") (pintype "input"))
      (node (ref "E13") (pin "13") (pinfunction "A2_13") (pintype "input"))
      (node (ref "E13") (pin "15") (pinfunction "A3_15") (pintype "input"))
      (node (ref "E13") (pin "17") (pinfunction "A4_17") (pintype "input"))
      (node (ref "E15") (pin "9") (pinfunction "Y1_9") (pintype "tri_state"))
      (node (ref "E16") (pin "16") (pinfunction "I/O4_16") (pintype "bidirectional"))
      (node (ref "SV2") (pin "3") (pinfunction "3_3") (pintype "passive"))
      (node (ref "SV3") (pin "3") (pinfunction "3_3") (pintype "passive"))
      (node (ref "SV4") (pin "3") (pinfunction "3_3") (pintype "passive"))
    )
    (net (code "91") (name "PWR_OK(0)") (class "Default")
      (node (ref "E5") (pin "13") (pinfunction "O_13") (pintype "open_collector"))
      (node (ref "R5") (pin "1") (pinfunction "1_1") (pintype "passive"))
      (node (ref "RESET") (pin "1") (pinfunction "1_1") (pintype "passive"))
    )
    (net (code "92") (name "RESET") (class "Default")
      (node (ref "E1") (pin "8") (pinfunction "O_8") (pintype "output"))
      (node (ref "E10") (pin "11") (pinfunction "CLK_11") (pintype "input"))
      (node (ref "E10") (pin "3") (pinfunction "CLK_3") (pintype "input"))
      (node (ref "E11") (pin "11") (pinfunction "CLK_11") (pintype "input"))
      (node (ref "E11") (pin "3") (pinfunction "CLK_3") (pintype "input"))
    )
    (net (code "93") (name "STROBE(0)") (class "Default")
      (node (ref "E5") (pin "4") (pinfunction "O_4") (pintype "open_collector"))
      (node (ref "H05") (pin "P2") (pinfunction "1_P2") (pintype "bidirectional"))
    )
    (net (code "94") (name "STROBE(1)") (class "Default")
      (node (ref "E10") (pin "5") (pinfunction "Q_5") (pintype "output"))
      (node (ref "E5") (pin "5") (pinfunction "I0_5") (pintype "input"))
      (node (ref "E5") (pin "6") (pinfunction "I1_6") (pintype "input"))
    )
    (net (code "95") (name "TP150") (class "Default")
      (node (ref "E10") (pin "10") (pinfunction "PRE_10") (pintype "input"))
      (node (ref "E8") (pin "6") (pinfunction "TAP3_6") (pintype "output"))
    )
    (net (code "96") (name "TP250") (class "Default")
      (node (ref "E7") (pin "1") (pinfunction "IN_1") (pintype "input"))
      (node (ref "E8") (pin "5") (pinfunction "TAP5_5") (pintype "output"))
    )
    (net (code "97") (name "TP300") (class "Default")
      (node (ref "E10") (pin "13") (pinfunction "CLR_13") (pintype "input"))
      (node (ref "E7") (pin "7") (pinfunction "TAP1_7") (pintype "output"))
    )
    (net (code "98") (name "TP500") (class "Default")
      (node (ref "E11") (pin "10") (pinfunction "PRE_10") (pintype "input"))
      (node (ref "E6") (pin "1") (pinfunction "IN_1") (pintype "input"))
      (node (ref "E7") (pin "5") (pinfunction "TAP5_5") (pintype "output"))
      (node (ref "E9") (pin "1") (pinfunction "CLR_1") (pintype "input"))
    )
    (net (code "99") (name "TP550") (class "Default")
      (node (ref "E11") (pin "13") (pinfunction "CLR_13") (pintype "input"))
      (node (ref "E6") (pin "7") (pinfunction "TAP1_7") (pintype "output"))
    )
    (net (code "100") (name "VCC") (class "Default")
      (node (ref "C10") (pin "1") (pinfunction "1_1") (pintype "passive"))
      (node (ref "C11") (pin "1") (pinfunction "1_1") (pintype "passive"))
      (node (ref "C12") (pin "1") (pinfunction "1_1") (pintype "passive"))
      (node (ref "C13") (pin "1") (pinfunction "1_1") (pintype "passive"))
      (node (ref "C14") (pin "1") (pinfunction "1_1") (pintype "passive"))
      (node (ref "C15") (pin "1") (pinfunction "1_1") (pintype "passive"))
      (node (ref "C16") (pin "1") (pinfunction "1_1") (pintype "passive"))
      (node (ref "C2") (pin "1") (pinfunction "1_1") (pintype "passive"))
      (node (ref "C3") (pin "1") (pinfunction "1_1") (pintype "passive"))
      (node (ref "C4") (pin "1") (pinfunction "1_1") (pintype "passive"))
      (node (ref "C5") (pin "1") (pinfunction "1_1") (pintype "passive"))
      (node (ref "C6") (pin "1") (pinfunction "1_1") (pintype "passive"))
      (node (ref "C7") (pin "1") (pinfunction "1_1") (pintype "passive"))
      (node (ref "C8") (pin "1") (pinfunction "1_1") (pintype "passive"))
      (node (ref "C9") (pin "1") (pinfunction "1_1") (pintype "passive"))
      (node (ref "D1") (pin "C") (pinfunction "C_C") (pintype "passive"))
      (node (ref "E16") (pin "28") (pinfunction "VCC_28") (pintype "power_in"))
      (node (ref "E17") (pin "28") (pinfunction "VCC_28") (pintype "power_in"))
      (node (ref "E19") (pin "6") (pinfunction "G1_6") (pintype "input"))
      (node (ref "E5") (pin "8") (pinfunction "I0_8") (pintype "input"))
      (node (ref "E5") (pin "9") (pinfunction "I1_9") (pintype "input"))
      (node (ref "E9") (pin "10") (pinfunction "PRE_10") (pintype "input"))
      (node (ref "E9") (pin "11") (pinfunction "CLK_11") (pintype "input"))
      (node (ref "E9") (pin "12") (pinfunction "D_12") (pintype "input"))
      (node (ref "E9") (pin "13") (pinfunction "CLR_13") (pintype "input"))
      (node (ref "E9") (pin "4") (pinfunction "PRE_4") (pintype "input"))
      (node (ref "R3") (pin "2") (pinfunction "2_2") (pintype "passive"))
      (node (ref "R5") (pin "2") (pinfunction "2_2") (pintype "passive"))
      (node (ref "SV1") (pin "49") (pinfunction "49_49") (pintype "passive"))
      (node (ref "SV1") (pin "50") (pinfunction "50_50") (pintype "passive"))
      (node (ref "SV2") (pin "49") (pinfunction "49_49") (pintype "passive"))
      (node (ref "SV2") (pin "50") (pinfunction "50_50") (pintype "passive"))
      (node (ref "SV3") (pin "49") (pinfunction "49_49") (pintype "passive"))
      (node (ref "SV3") (pin "50") (pinfunction "50_50") (pintype "passive"))
      (node (ref "SV4") (pin "49") (pinfunction "49_49") (pintype "passive"))
      (node (ref "SV4") (pin "50") (pinfunction "50_50") (pintype "passive"))
      (node (ref "SV5") (pin "49") (pinfunction "49_49") (pintype "passive"))
      (node (ref "SV5") (pin "50") (pinfunction "50_50") (pintype "passive"))
      (node (ref "X1") (pin "1") (pinfunction "KL_1") (pintype "passive"))
    )
    (net (code "101") (name "WE(0)") (class "Default")
      (node (ref "E10") (pin "8") (pinfunction "~{Q}_8") (pintype "output"))
      (node (ref "E14") (pin "1") (pinfunction "G_1") (pintype "input"))
      (node (ref "E14") (pin "19") (pinfunction "G_19") (pintype "input"))
      (node (ref "E15") (pin "1") (pinfunction "G_1") (pintype "input"))
      (node (ref "E15") (pin "19") (pinfunction "G_19") (pintype "input"))
      (node (ref "E16") (pin "27") (pinfunction "~{WE}_27") (pintype "input"))
      (node (ref "E17") (pin "27") (pinfunction "~{WE}_27") (pintype "input"))
      (node (ref "SV2") (pin "32") (pinfunction "32_32") (pintype "passive"))
      (node (ref "SV3") (pin "32") (pinfunction "32_32") (pintype "passive"))
      (node (ref "SV5") (pin "32") (pinfunction "32_32") (pintype "passive"))
    )
    (net (code "102") (name "unconnected-(E2A-TAP1-Pad7)") (class "Default")
      (node (ref "E2") (pin "7") (pinfunction "TAP1_7") (pintype "output"))
    )
    (net (code "103") (name "unconnected-(E2A-TAP2-Pad2)") (class "Default")
      (node (ref "E2") (pin "2") (pinfunction "TAP2_2") (pintype "output"))
    )
    (net (code "104") (name "unconnected-(E2A-TAP4-Pad3)") (class "Default")
      (node (ref "E2") (pin "3") (pinfunction "TAP4_3") (pintype "output"))
    )
    (net (code "105") (name "unconnected-(E2A-TAP5-Pad5)") (class "Default")
      (node (ref "E2") (pin "5") (pinfunction "TAP5_5") (pintype "output"))
    )
    (net (code "106") (name "unconnected-(E3A-TAP1-Pad7)") (class "Default")
      (node (ref "E3") (pin "7") (pinfunction "TAP1_7") (pintype "output"))
    )
    (net (code "107") (name "unconnected-(E3A-TAP4-Pad3)") (class "Default")
      (node (ref "E3") (pin "3") (pinfunction "TAP4_3") (pintype "output"))
    )
    (net (code "108") (name "unconnected-(E4A-TAP1-Pad7)") (class "Default")
      (node (ref "E4") (pin "7") (pinfunction "TAP1_7") (pintype "output"))
    )
    (net (code "109") (name "unconnected-(E4A-TAP4-Pad3)") (class "Default")
      (node (ref "E4") (pin "3") (pinfunction "TAP4_3") (pintype "output"))
    )
    (net (code "110") (name "unconnected-(E5C-O-Pad10)") (class "Default")
      (node (ref "E5") (pin "10") (pinfunction "O_10") (pintype "open_collector"))
    )
    (net (code "111") (name "unconnected-(E6A-TAP2-Pad2)") (class "Default")
      (node (ref "E6") (pin "2") (pinfunction "TAP2_2") (pintype "output"))
    )
    (net (code "112") (name "unconnected-(E6A-TAP3-Pad6)") (class "Default")
      (node (ref "E6") (pin "6") (pinfunction "TAP3_6") (pintype "output"))
    )
    (net (code "113") (name "unconnected-(E6A-TAP4-Pad3)") (class "Default")
      (node (ref "E6") (pin "3") (pinfunction "TAP4_3") (pintype "output"))
    )
    (net (code "114") (name "unconnected-(E6A-TAP5-Pad5)") (class "Default")
      (node (ref "E6") (pin "5") (pinfunction "TAP5_5") (pintype "output"))
    )
    (net (code "115") (name "unconnected-(E7A-TAP2-Pad2)") (class "Default")
      (node (ref "E7") (pin "2") (pinfunction "TAP2_2") (pintype "output"))
    )
    (net (code "116") (name "unconnected-(E7A-TAP3-Pad6)") (class "Default")
      (node (ref "E7") (pin "6") (pinfunction "TAP3_6") (pintype "output"))
    )
    (net (code "117") (name "unconnected-(E7A-TAP4-Pad3)") (class "Default")
      (node (ref "E7") (pin "3") (pinfunction "TAP4_3") (pintype "output"))
    )
    (net (code "118") (name "unconnected-(E8A-TAP1-Pad7)") (class "Default")
      (node (ref "E8") (pin "7") (pinfunction "TAP1_7") (pintype "output"))
    )
    (net (code "119") (name "unconnected-(E8A-TAP2-Pad2)") (class "Default")
      (node (ref "E8") (pin "2") (pinfunction "TAP2_2") (pintype "output"))
    )
    (net (code "120") (name "unconnected-(E8A-TAP4-Pad3)") (class "Default")
      (node (ref "E8") (pin "3") (pinfunction "TAP4_3") (pintype "output"))
    )
    (net (code "121") (name "unconnected-(E9A-Q-Pad5)") (class "Default")
      (node (ref "E9") (pin "5") (pinfunction "Q_5") (pintype "output"))
    )
    (net (code "122") (name "unconnected-(E9B-Q-Pad9)") (class "Default")
      (node (ref "E9") (pin "9") (pinfunction "Q_9") (pintype "output"))
    )
    (net (code "123") (name "unconnected-(E9B-~{Q}-Pad8)") (class "Default")
      (node (ref "E9") (pin "8") (pinfunction "~{Q}_8") (pintype "output"))
    )
    (net (code "124") (name "unconnected-(E10A-~{Q}-Pad6)") (class "Default")
      (node (ref "E10") (pin "6") (pinfunction "~{Q}_6") (pintype "output"))
    )
    (net (code "125") (name "unconnected-(E10B-Q-Pad9)") (class "Default")
      (node (ref "E10") (pin "9") (pinfunction "Q_9") (pintype "output"))
    )
    (net (code "126") (name "unconnected-(E11A-Q-Pad5)") (class "Default")
      (node (ref "E11") (pin "5") (pinfunction "Q_5") (pintype "output"))
    )
    (net (code "127") (name "unconnected-(E11B-~{Q}-Pad8)") (class "Default")
      (node (ref "E11") (pin "8") (pinfunction "~{Q}_8") (pintype "output"))
    )
    (net (code "128") (name "unconnected-(E13B-Y2-Pad7)") (class "Default")
      (node (ref "E13") (pin "7") (pinfunction "Y2_7") (pintype "tri_state"))
    )
    (net (code "129") (name "unconnected-(E13B-Y3-Pad5)") (class "Default")
      (node (ref "E13") (pin "5") (pinfunction "Y3_5") (pintype "tri_state"))
    )
    (net (code "130") (name "unconnected-(E13B-Y4-Pad3)") (class "Default")
      (node (ref "E13") (pin "3") (pinfunction "Y4_3") (pintype "tri_state"))
    )
    (net (code "131") (name "unconnected-(E15B-Y2-Pad7)") (class "Default")
      (node (ref "E15") (pin "7") (pinfunction "Y2_7") (pintype "tri_state"))
    )
    (net (code "132") (name "unconnected-(E15B-Y3-Pad5)") (class "Default")
      (node (ref "E15") (pin "5") (pinfunction "Y3_5") (pintype "tri_state"))
    )
    (net (code "133") (name "unconnected-(E15B-Y4-Pad3)") (class "Default")
      (node (ref "E15") (pin "3") (pinfunction "Y4_3") (pintype "tri_state"))
    )
    (net (code "134") (name "unconnected-(E16-I{slash}O5-Pad17)") (class "Default")
      (node (ref "E16") (pin "17") (pinfunction "I/O5_17") (pintype "bidirectional"))
    )
    (net (code "135") (name "unconnected-(E16-I{slash}O6-Pad18)") (class "Default")
      (node (ref "E16") (pin "18") (pinfunction "I/O6_18") (pintype "bidirectional"))
    )
    (net (code "136") (name "unconnected-(E16-I{slash}O7-Pad19)") (class "Default")
      (node (ref "E16") (pin "19") (pinfunction "I/O7_19") (pintype "bidirectional"))
    )
    (net (code "137") (name "unconnected-(SV1-Pad3)") (class "Default")
      (node (ref "SV1") (pin "3") (pinfunction "3_3") (pintype "passive"))
    )
    (net (code "138") (name "unconnected-(SV1-Pad4)") (class "Default")
      (node (ref "SV1") (pin "4") (pinfunction "4_4") (pintype "passive"))
    )
    (net (code "139") (name "unconnected-(SV1-Pad5)") (class "Default")
      (node (ref "SV1") (pin "5") (pinfunction "5_5") (pintype "passive"))
    )
    (net (code "140") (name "unconnected-(SV1-Pad6)") (class "Default")
      (node (ref "SV1") (pin "6") (pinfunction "6_6") (pintype "passive"))
    )
    (net (code "141") (name "unconnected-(SV1-Pad7)") (class "Default")
      (node (ref "SV1") (pin "7") (pinfunction "7_7") (pintype "passive"))
    )
    (net (code "142") (name "unconnected-(SV1-Pad8)") (class "Default")
      (node (ref "SV1") (pin "8") (pinfunction "8_8") (pintype "passive"))
    )
    (net (code "143") (name "unconnected-(SV1-Pad9)") (class "Default")
      (node (ref "SV1") (pin "9") (pinfunction "9_9") (pintype "passive"))
    )
    (net (code "144") (name "unconnected-(SV1-Pad10)") (class "Default")
      (node (ref "SV1") (pin "10") (pinfunction "10_10") (pintype "passive"))
    )
    (net (code "145") (name "unconnected-(SV1-Pad11)") (class "Default")
      (node (ref "SV1") (pin "11") (pinfunction "11_11") (pintype "passive"))
    )
    (net (code "146") (name "unconnected-(SV1-Pad12)") (class "Default")
      (node (ref "SV1") (pin "12") (pinfunction "12_12") (pintype "passive"))
    )
    (net (code "147") (name "unconnected-(SV1-Pad13)") (class "Default")
      (node (ref "SV1") (pin "13") (pinfunction "13_13") (pintype "passive"))
    )
    (net (code "148") (name "unconnected-(SV1-Pad14)") (class "Default")
      (node (ref "SV1") (pin "14") (pinfunction "14_14") (pintype "passive"))
    )
    (net (code "149") (name "unconnected-(SV1-Pad15)") (class "Default")
      (node (ref "SV1") (pin "15") (pinfunction "15_15") (pintype "passive"))
    )
    (net (code "150") (name "unconnected-(SV1-Pad16)") (class "Default")
      (node (ref "SV1") (pin "16") (pinfunction "16_16") (pintype "passive"))
    )
    (net (code "151") (name "unconnected-(SV1-Pad17)") (class "Default")
      (node (ref "SV1") (pin "17") (pinfunction "17_17") (pintype "passive"))
    )
    (net (code "152") (name "unconnected-(SV1-Pad18)") (class "Default")
      (node (ref "SV1") (pin "18") (pinfunction "18_18") (pintype "passive"))
    )
    (net (code "153") (name "unconnected-(SV1-Pad19)") (class "Default")
      (node (ref "SV1") (pin "19") (pinfunction "19_19") (pintype "passive"))
    )
    (net (code "154") (name "unconnected-(SV1-Pad21)") (class "Default")
      (node (ref "SV1") (pin "21") (pinfunction "21_21") (pintype "passive"))
    )
    (net (code "155") (name "unconnected-(SV1-Pad22)") (class "Default")
      (node (ref "SV1") (pin "22") (pinfunction "22_22") (pintype "passive"))
    )
    (net (code "156") (name "unconnected-(SV1-Pad23)") (class "Default")
      (node (ref "SV1") (pin "23") (pinfunction "23_23") (pintype "passive"))
    )
    (net (code "157") (name "unconnected-(SV1-Pad25)") (class "Default")
      (node (ref "SV1") (pin "25") (pinfunction "25_25") (pintype "passive"))
    )
    (net (code "158") (name "unconnected-(SV1-Pad32)") (class "Default")
      (node (ref "SV1") (pin "32") (pinfunction "32_32") (pintype "passive"))
    )
    (net (code "159") (name "unconnected-(SV1-Pad35)") (class "Default")
      (node (ref "SV1") (pin "35") (pinfunction "35_35") (pintype "passive"))
    )
    (net (code "160") (name "unconnected-(SV1-Pad36)") (class "Default")
      (node (ref "SV1") (pin "36") (pinfunction "36_36") (pintype "passive"))
    )
    (net (code "161") (name "unconnected-(SV1-Pad37)") (class "Default")
      (node (ref "SV1") (pin "37") (pinfunction "37_37") (pintype "passive"))
    )
    (net (code "162") (name "unconnected-(SV1-Pad38)") (class "Default")
      (node (ref "SV1") (pin "38") (pinfunction "38_38") (pintype "passive"))
    )
    (net (code "163") (name "unconnected-(SV1-Pad39)") (class "Default")
      (node (ref "SV1") (pin "39") (pinfunction "39_39") (pintype "passive"))
    )
    (net (code "164") (name "unconnected-(SV1-Pad40)") (class "Default")
      (node (ref "SV1") (pin "40") (pinfunction "40_40") (pintype "passive"))
    )
    (net (code "165") (name "unconnected-(SV1-Pad41)") (class "Default")
      (node (ref "SV1") (pin "41") (pinfunction "41_41") (pintype "passive"))
    )
    (net (code "166") (name "unconnected-(SV1-Pad42)") (class "Default")
      (node (ref "SV1") (pin "42") (pinfunction "42_42") (pintype "passive"))
    )
    (net (code "167") (name "unconnected-(SV1-Pad45)") (class "Default")
      (node (ref "SV1") (pin "45") (pinfunction "45_45") (pintype "passive"))
    )
    (net (code "168") (name "unconnected-(SV1-Pad47)") (class "Default")
      (node (ref "SV1") (pin "47") (pinfunction "47_47") (pintype "passive"))
    )
    (net (code "169") (name "unconnected-(SV1-Pad48)") (class "Default")
      (node (ref "SV1") (pin "48") (pinfunction "48_48") (pintype "passive"))
    )
    (net (code "170") (name "unconnected-(SV2-Pad34)") (class "Default")
      (node (ref "SV2") (pin "34") (pinfunction "34_34") (pintype "passive"))
    )
    (net (code "171") (name "unconnected-(SV2-Pad37)") (class "Default")
      (node (ref "SV2") (pin "37") (pinfunction "37_37") (pintype "passive"))
    )
    (net (code "172") (name "unconnected-(SV2-Pad39)") (class "Default")
      (node (ref "SV2") (pin "39") (pinfunction "39_39") (pintype "passive"))
    )
    (net (code "173") (name "unconnected-(SV2-Pad40)") (class "Default")
      (node (ref "SV2") (pin "40") (pinfunction "40_40") (pintype "passive"))
    )
    (net (code "174") (name "unconnected-(SV2-Pad41)") (class "Default")
      (node (ref "SV2") (pin "41") (pinfunction "41_41") (pintype "passive"))
    )
    (net (code "175") (name "unconnected-(SV2-Pad42)") (class "Default")
      (node (ref "SV2") (pin "42") (pinfunction "42_42") (pintype "passive"))
    )
    (net (code "176") (name "unconnected-(SV2-Pad43)") (class "Default")
      (node (ref "SV2") (pin "43") (pinfunction "43_43") (pintype "passive"))
    )
    (net (code "177") (name "unconnected-(SV2-Pad44)") (class "Default")
      (node (ref "SV2") (pin "44") (pinfunction "44_44") (pintype "passive"))
    )
    (net (code "178") (name "unconnected-(SV2-Pad45)") (class "Default")
      (node (ref "SV2") (pin "45") (pinfunction "45_45") (pintype "passive"))
    )
    (net (code "179") (name "unconnected-(SV2-Pad46)") (class "Default")
      (node (ref "SV2") (pin "46") (pinfunction "46_46") (pintype "passive"))
    )
    (net (code "180") (name "unconnected-(SV2-Pad47)") (class "Default")
      (node (ref "SV2") (pin "47") (pinfunction "47_47") (pintype "passive"))
    )
    (net (code "181") (name "unconnected-(SV2-Pad48)") (class "Default")
      (node (ref "SV2") (pin "48") (pinfunction "48_48") (pintype "passive"))
    )
    (net (code "182") (name "unconnected-(SV3-Pad15)") (class "Default")
      (node (ref "SV3") (pin "15") (pinfunction "15_15") (pintype "passive"))
    )
    (net (code "183") (name "unconnected-(SV3-Pad17)") (class "Default")
      (node (ref "SV3") (pin "17") (pinfunction "17_17") (pintype "passive"))
    )
    (net (code "184") (name "unconnected-(SV3-Pad18)") (class "Default")
      (node (ref "SV3") (pin "18") (pinfunction "18_18") (pintype "passive"))
    )
    (net (code "185") (name "unconnected-(SV3-Pad19)") (class "Default")
      (node (ref "SV3") (pin "19") (pinfunction "19_19") (pintype "passive"))
    )
    (net (code "186") (name "unconnected-(SV3-Pad20)") (class "Default")
      (node (ref "SV3") (pin "20") (pinfunction "20_20") (pintype "passive"))
    )
    (net (code "187") (name "unconnected-(SV3-Pad21)") (class "Default")
      (node (ref "SV3") (pin "21") (pinfunction "21_21") (pintype "passive"))
    )
    (net (code "188") (name "unconnected-(SV3-Pad22)") (class "Default")
      (node (ref "SV3") (pin "22") (pinfunction "22_22") (pintype "passive"))
    )
    (net (code "189") (name "unconnected-(SV3-Pad23)") (class "Default")
      (node (ref "SV3") (pin "23") (pinfunction "23_23") (pintype "passive"))
    )
    (net (code "190") (name "unconnected-(SV3-Pad24)") (class "Default")
      (node (ref "SV3") (pin "24") (pinfunction "24_24") (pintype "passive"))
    )
    (net (code "191") (name "unconnected-(SV3-Pad25)") (class "Default")
      (node (ref "SV3") (pin "25") (pinfunction "25_25") (pintype "passive"))
    )
    (net (code "192") (name "unconnected-(SV3-Pad26)") (class "Default")
      (node (ref "SV3") (pin "26") (pinfunction "26_26") (pintype "passive"))
    )
    (net (code "193") (name "unconnected-(SV3-Pad27)") (class "Default")
      (node (ref "SV3") (pin "27") (pinfunction "27_27") (pintype "passive"))
    )
    (net (code "194") (name "unconnected-(SV3-Pad28)") (class "Default")
      (node (ref "SV3") (pin "28") (pinfunction "28_28") (pintype "passive"))
    )
    (net (code "195") (name "unconnected-(SV3-Pad29)") (class "Default")
      (node (ref "SV3") (pin "29") (pinfunction "29_29") (pintype "passive"))
    )
    (net (code "196") (name "unconnected-(SV3-Pad34)") (class "Default")
      (node (ref "SV3") (pin "34") (pinfunction "34_34") (pintype "passive"))
    )
    (net (code "197") (name "unconnected-(SV3-Pad37)") (class "Default")
      (node (ref "SV3") (pin "37") (pinfunction "37_37") (pintype "passive"))
    )
    (net (code "198") (name "unconnected-(SV3-Pad39)") (class "Default")
      (node (ref "SV3") (pin "39") (pinfunction "39_39") (pintype "passive"))
    )
    (net (code "199") (name "unconnected-(SV3-Pad40)") (class "Default")
      (node (ref "SV3") (pin "40") (pinfunction "40_40") (pintype "passive"))
    )
    (net (code "200") (name "unconnected-(SV3-Pad41)") (class "Default")
      (node (ref "SV3") (pin "41") (pinfunction "41_41") (pintype "passive"))
    )
    (net (code "201") (name "unconnected-(SV3-Pad45)") (class "Default")
      (node (ref "SV3") (pin "45") (pinfunction "45_45") (pintype "passive"))
    )
    (net (code "202") (name "unconnected-(SV3-Pad47)") (class "Default")
      (node (ref "SV3") (pin "47") (pinfunction "47_47") (pintype "passive"))
    )
    (net (code "203") (name "unconnected-(SV3-Pad48)") (class "Default")
      (node (ref "SV3") (pin "48") (pinfunction "48_48") (pintype "passive"))
    )
    (net (code "204") (name "unconnected-(SV4-Pad15)") (class "Default")
      (node (ref "SV4") (pin "15") (pinfunction "15_15") (pintype "passive"))
    )
    (net (code "205") (name "unconnected-(SV4-Pad17)") (class "Default")
      (node (ref "SV4") (pin "17") (pinfunction "17_17") (pintype "passive"))
    )
    (net (code "206") (name "unconnected-(SV4-Pad18)") (class "Default")
      (node (ref "SV4") (pin "18") (pinfunction "18_18") (pintype "passive"))
    )
    (net (code "207") (name "unconnected-(SV4-Pad19)") (class "Default")
      (node (ref "SV4") (pin "19") (pinfunction "19_19") (pintype "passive"))
    )
    (net (code "208") (name "unconnected-(SV4-Pad20)") (class "Default")
      (node (ref "SV4") (pin "20") (pinfunction "20_20") (pintype "passive"))
    )
    (net (code "209") (name "unconnected-(SV4-Pad21)") (class "Default")
      (node (ref "SV4") (pin "21") (pinfunction "21_21") (pintype "passive"))
    )
    (net (code "210") (name "unconnected-(SV4-Pad23)") (class "Default")
      (node (ref "SV4") (pin "23") (pinfunction "23_23") (pintype "passive"))
    )
    (net (code "211") (name "unconnected-(SV4-Pad24)") (class "Default")
      (node (ref "SV4") (pin "24") (pinfunction "24_24") (pintype "passive"))
    )
    (net (code "212") (name "unconnected-(SV4-Pad25)") (class "Default")
      (node (ref "SV4") (pin "25") (pinfunction "25_25") (pintype "passive"))
    )
    (net (code "213") (name "unconnected-(SV4-Pad26)") (class "Default")
      (node (ref "SV4") (pin "26") (pinfunction "26_26") (pintype "passive"))
    )
    (net (code "214") (name "unconnected-(SV4-Pad27)") (class "Default")
      (node (ref "SV4") (pin "27") (pinfunction "27_27") (pintype "passive"))
    )
    (net (code "215") (name "unconnected-(SV4-Pad28)") (class "Default")
      (node (ref "SV4") (pin "28") (pinfunction "28_28") (pintype "passive"))
    )
    (net (code "216") (name "unconnected-(SV4-Pad29)") (class "Default")
      (node (ref "SV4") (pin "29") (pinfunction "29_29") (pintype "passive"))
    )
    (net (code "217") (name "unconnected-(SV4-Pad30)") (class "Default")
      (node (ref "SV4") (pin "30") (pinfunction "30_30") (pintype "passive"))
    )
    (net (code "218") (name "unconnected-(SV4-Pad31)") (class "Default")
      (node (ref "SV4") (pin "31") (pinfunction "31_31") (pintype "passive"))
    )
    (net (code "219") (name "unconnected-(SV4-Pad32)") (class "Default")
      (node (ref "SV4") (pin "32") (pinfunction "32_32") (pintype "passive"))
    )
    (net (code "220") (name "unconnected-(SV4-Pad33)") (class "Default")
      (node (ref "SV4") (pin "33") (pinfunction "33_33") (pintype "passive"))
    )
    (net (code "221") (name "unconnected-(SV4-Pad34)") (class "Default")
      (node (ref "SV4") (pin "34") (pinfunction "34_34") (pintype "passive"))
    )
    (net (code "222") (name "unconnected-(SV4-Pad35)") (class "Default")
      (node (ref "SV4") (pin "35") (pinfunction "35_35") (pintype "passive"))
    )
    (net (code "223") (name "unconnected-(SV4-Pad36)") (class "Default")
      (node (ref "SV4") (pin "36") (pinfunction "36_36") (pintype "passive"))
    )
    (net (code "224") (name "unconnected-(SV4-Pad38)") (class "Default")
      (node (ref "SV4") (pin "38") (pinfunction "38_38") (pintype "passive"))
    )
    (net (code "225") (name "unconnected-(SV4-Pad42)") (class "Default")
      (node (ref "SV4") (pin "42") (pinfunction "42_42") (pintype "passive"))
    )
    (net (code "226") (name "unconnected-(SV4-Pad43)") (class "Default")
      (node (ref "SV4") (pin "43") (pinfunction "43_43") (pintype "passive"))
    )
    (net (code "227") (name "unconnected-(SV4-Pad44)") (class "Default")
      (node (ref "SV4") (pin "44") (pinfunction "44_44") (pintype "passive"))
    )
    (net (code "228") (name "unconnected-(SV4-Pad45)") (class "Default")
      (node (ref "SV4") (pin "45") (pinfunction "45_45") (pintype "passive"))
    )
    (net (code "229") (name "unconnected-(SV4-Pad46)") (class "Default")
      (node (ref "SV4") (pin "46") (pinfunction "46_46") (pintype "passive"))
    )
    (net (code "230") (name "unconnected-(SV4-Pad47)") (class "Default")
      (node (ref "SV4") (pin "47") (pinfunction "47_47") (pintype "passive"))
    )
    (net (code "231") (name "unconnected-(SV4-Pad48)") (class "Default")
      (node (ref "SV4") (pin "48") (pinfunction "48_48") (pintype "passive"))
    )
    (net (code "232") (name "unconnected-(SV5-Pad3)") (class "Default")
      (node (ref "SV5") (pin "3") (pinfunction "3_3") (pintype "passive"))
    )
    (net (code "233") (name "unconnected-(SV5-Pad4)") (class "Default")
      (node (ref "SV5") (pin "4") (pinfunction "4_4") (pintype "passive"))
    )
    (net (code "234") (name "unconnected-(SV5-Pad5)") (class "Default")
      (node (ref "SV5") (pin "5") (pinfunction "5_5") (pintype "passive"))
    )
    (net (code "235") (name "unconnected-(SV5-Pad6)") (class "Default")
      (node (ref "SV5") (pin "6") (pinfunction "6_6") (pintype "passive"))
    )
    (net (code "236") (name "unconnected-(SV5-Pad7)") (class "Default")
      (node (ref "SV5") (pin "7") (pinfunction "7_7") (pintype "passive"))
    )
    (net (code "237") (name "unconnected-(SV5-Pad8)") (class "Default")
      (node (ref "SV5") (pin "8") (pinfunction "8_8") (pintype "passive"))
    )
    (net (code "238") (name "unconnected-(SV5-Pad9)") (class "Default")
      (node (ref "SV5") (pin "9") (pinfunction "9_9") (pintype "passive"))
    )
    (net (code "239") (name "unconnected-(SV5-Pad10)") (class "Default")
      (node (ref "SV5") (pin "10") (pinfunction "10_10") (pintype "passive"))
    )
    (net (code "240") (name "unconnected-(SV5-Pad11)") (class "Default")
      (node (ref "SV5") (pin "11") (pinfunction "11_11") (pintype "passive"))
    )
    (net (code "241") (name "unconnected-(SV5-Pad12)") (class "Default")
      (node (ref "SV5") (pin "12") (pinfunction "12_12") (pintype "passive"))
    )
    (net (code "242") (name "unconnected-(SV5-Pad13)") (class "Default")
      (node (ref "SV5") (pin "13") (pinfunction "13_13") (pintype "passive"))
    )
    (net (code "243") (name "unconnected-(SV5-Pad14)") (class "Default")
      (node (ref "SV5") (pin "14") (pinfunction "14_14") (pintype "passive"))
    )
    (net (code "244") (name "unconnected-(SV5-Pad15)") (class "Default")
      (node (ref "SV5") (pin "15") (pinfunction "15_15") (pintype "passive"))
    )
    (net (code "245") (name "unconnected-(SV5-Pad16)") (class "Default")
      (node (ref "SV5") (pin "16") (pinfunction "16_16") (pintype "passive"))
    )
    (net (code "246") (name "unconnected-(SV5-Pad17)") (class "Default")
      (node (ref "SV5") (pin "17") (pinfunction "17_17") (pintype "passive"))
    )
    (net (code "247") (name "unconnected-(SV5-Pad19)") (class "Default")
      (node (ref "SV5") (pin "19") (pinfunction "19_19") (pintype "passive"))
    )
    (net (code "248") (name "unconnected-(SV5-Pad20)") (class "Default")
      (node (ref "SV5") (pin "20") (pinfunction "20_20") (pintype "passive"))
    )
    (net (code "249") (name "unconnected-(SV5-Pad21)") (class "Default")
      (node (ref "SV5") (pin "21") (pinfunction "21_21") (pintype "passive"))
    )
    (net (code "250") (name "unconnected-(SV5-Pad23)") (class "Default")
      (node (ref "SV5") (pin "23") (pinfunction "23_23") (pintype "passive"))
    )
    (net (code "251") (name "unconnected-(SV5-Pad24)") (class "Default")
      (node (ref "SV5") (pin "24") (pinfunction "24_24") (pintype "passive"))
    )
    (net (code "252") (name "unconnected-(SV5-Pad25)") (class "Default")
      (node (ref "SV5") (pin "25") (pinfunction "25_25") (pintype "passive"))
    )
    (net (code "253") (name "unconnected-(SV5-Pad26)") (class "Default")
      (node (ref "SV5") (pin "26") (pinfunction "26_26") (pintype "passive"))
    )
    (net (code "254") (name "unconnected-(SV5-Pad27)") (class "Default")
      (node (ref "SV5") (pin "27") (pinfunction "27_27") (pintype "passive"))
    )
    (net (code "255") (name "unconnected-(SV5-Pad28)") (class "Default")
      (node (ref "SV5") (pin "28") (pinfunction "28_28") (pintype "passive"))
    )
    (net (code "256") (name "unconnected-(SV5-Pad29)") (class "Default")
      (node (ref "SV5") (pin "29") (pinfunction "29_29") (pintype "passive"))
    )
    (net (code "257") (name "unconnected-(SV5-Pad30)") (class "Default")
      (node (ref "SV5") (pin "30") (pinfunction "30_30") (pintype "passive"))
    )
    (net (code "258") (name "unconnected-(SV5-Pad31)") (class "Default")
      (node (ref "SV5") (pin "31") (pinfunction "31_31") (pintype "passive"))
    )
    (net (code "259") (name "unconnected-(SV5-Pad33)") (class "Default")
      (node (ref "SV5") (pin "33") (pinfunction "33_33") (pintype "passive"))
    )
    (net (code "260") (name "unconnected-(SV5-Pad35)") (class "Default")
      (node (ref "SV5") (pin "35") (pinfunction "35_35") (pintype "passive"))
    )
    (net (code "261") (name "unconnected-(SV5-Pad36)") (class "Default")
      (node (ref "SV5") (pin "36") (pinfunction "36_36") (pintype "passive"))
    )
    (net (code "262") (name "unconnected-(SV5-Pad38)") (class "Default")
      (node (ref "SV5") (pin "38") (pinfunction "38_38") (pintype "passive"))
    )
    (net (code "263") (name "unconnected-(SV5-Pad43)") (class "Default")
      (node (ref "SV5") (pin "43") (pinfunction "43_43") (pintype "passive"))
    )
    (net (code "264") (name "unconnected-(SV5-Pad44)") (class "Default")
      (node (ref "SV5") (pin "44") (pinfunction "44_44") (pintype "passive"))
    )
    (net (code "265") (name "unconnected-(SV5-Pad45)") (class "Default")
      (node (ref "SV5") (pin "45") (pinfunction "45_45") (pintype "passive"))
    )
    (net (code "266") (name "unconnected-(SV5-Pad46)") (class "Default")
      (node (ref "SV5") (pin "46") (pinfunction "46_46") (pintype "passive"))
    )
    (net (code "267") (name "unconnected-(SV5-Pad47)") (class "Default")
      (node (ref "SV5") (pin "47") (pinfunction "47_47") (pintype "passive"))
    )
    (net (code "268") (name "unconnected-(SV5-Pad48)") (class "Default")
      (node (ref "SV5") (pin "48") (pinfunction "48_48") (pintype "passive"))
    )
  )
)
